# module.net
KiCad netlist of a schematic drawn in EAGLE
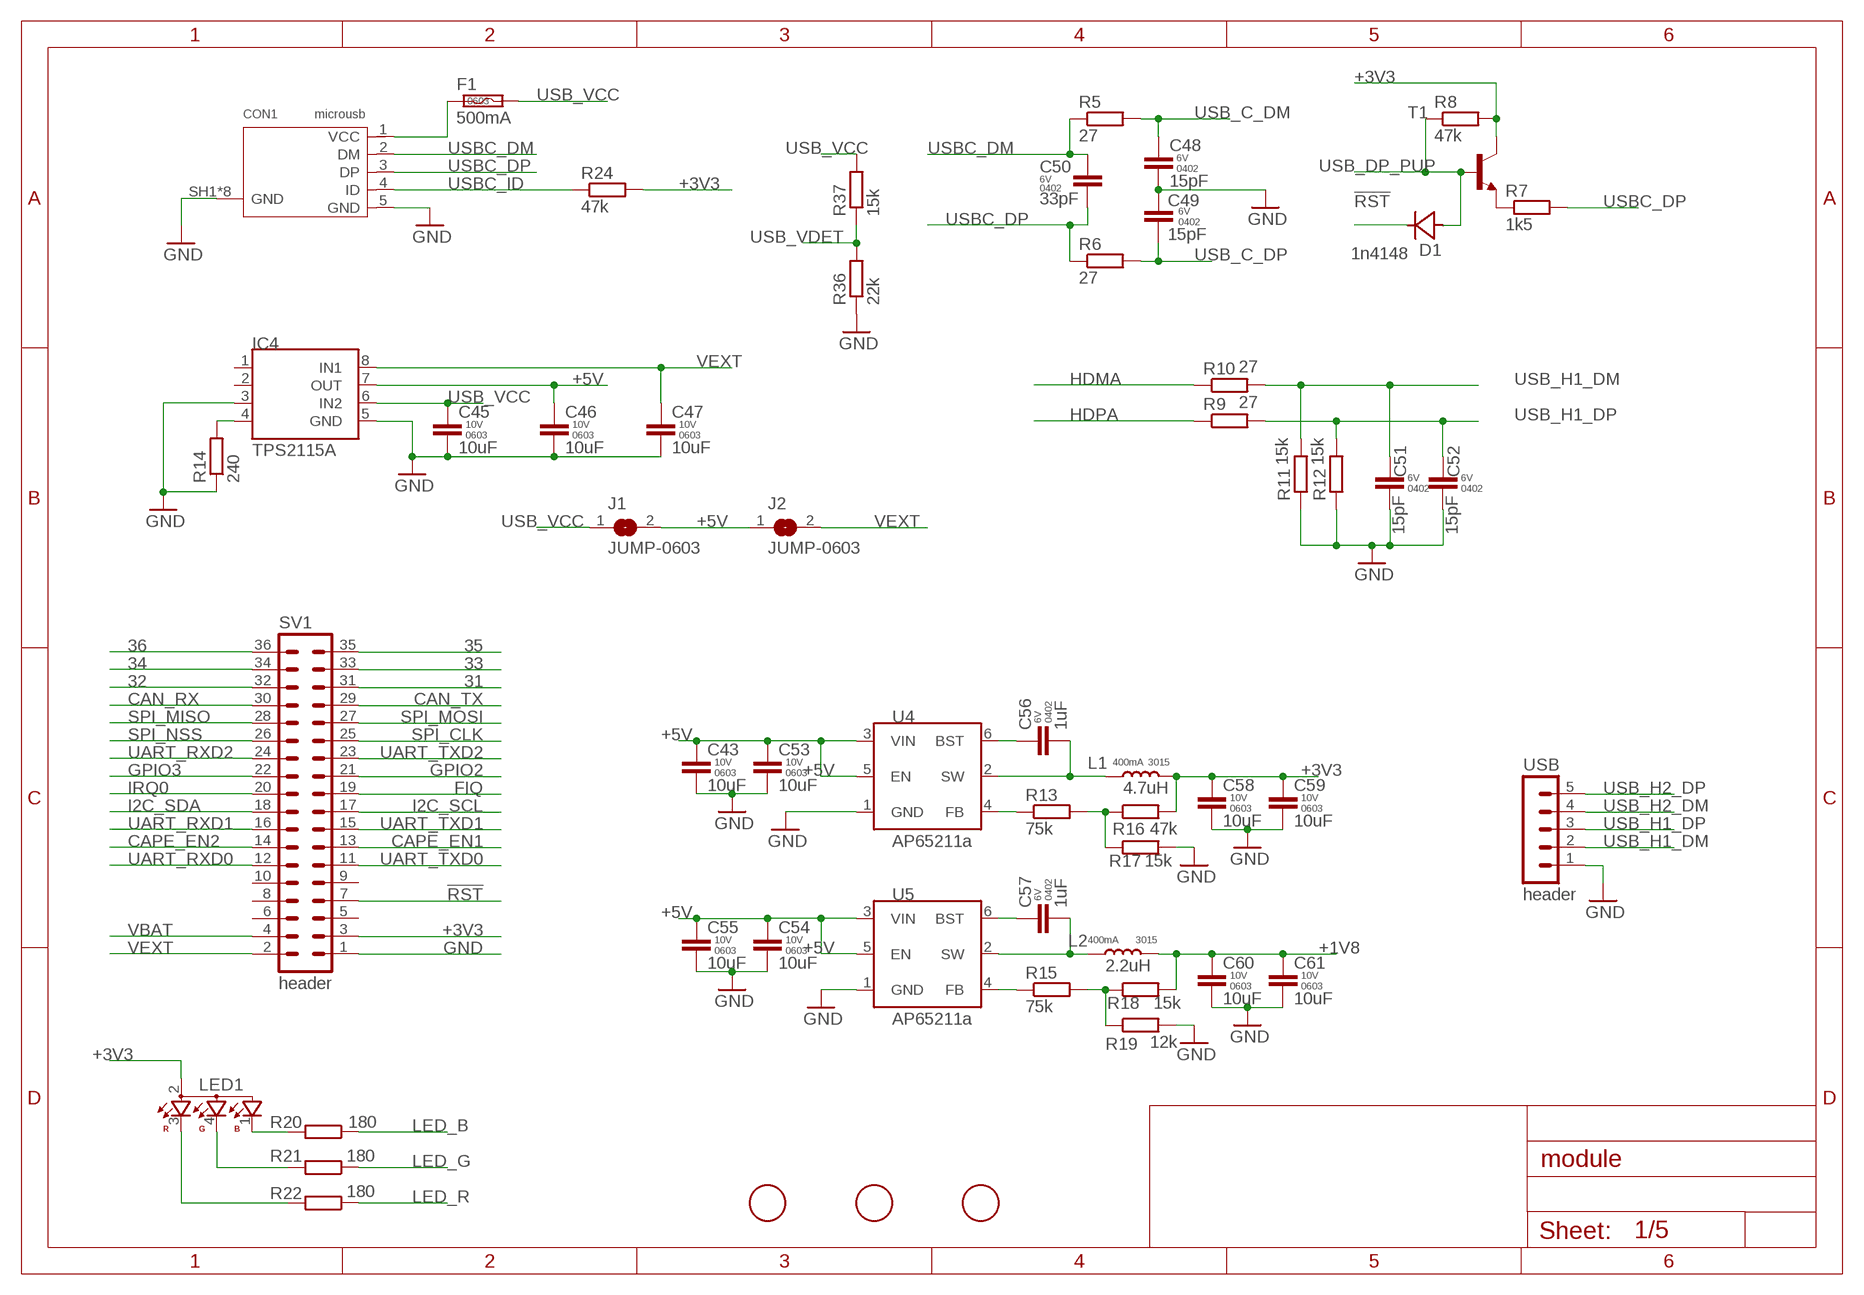
[diagram p0: schematic, sheet 1]
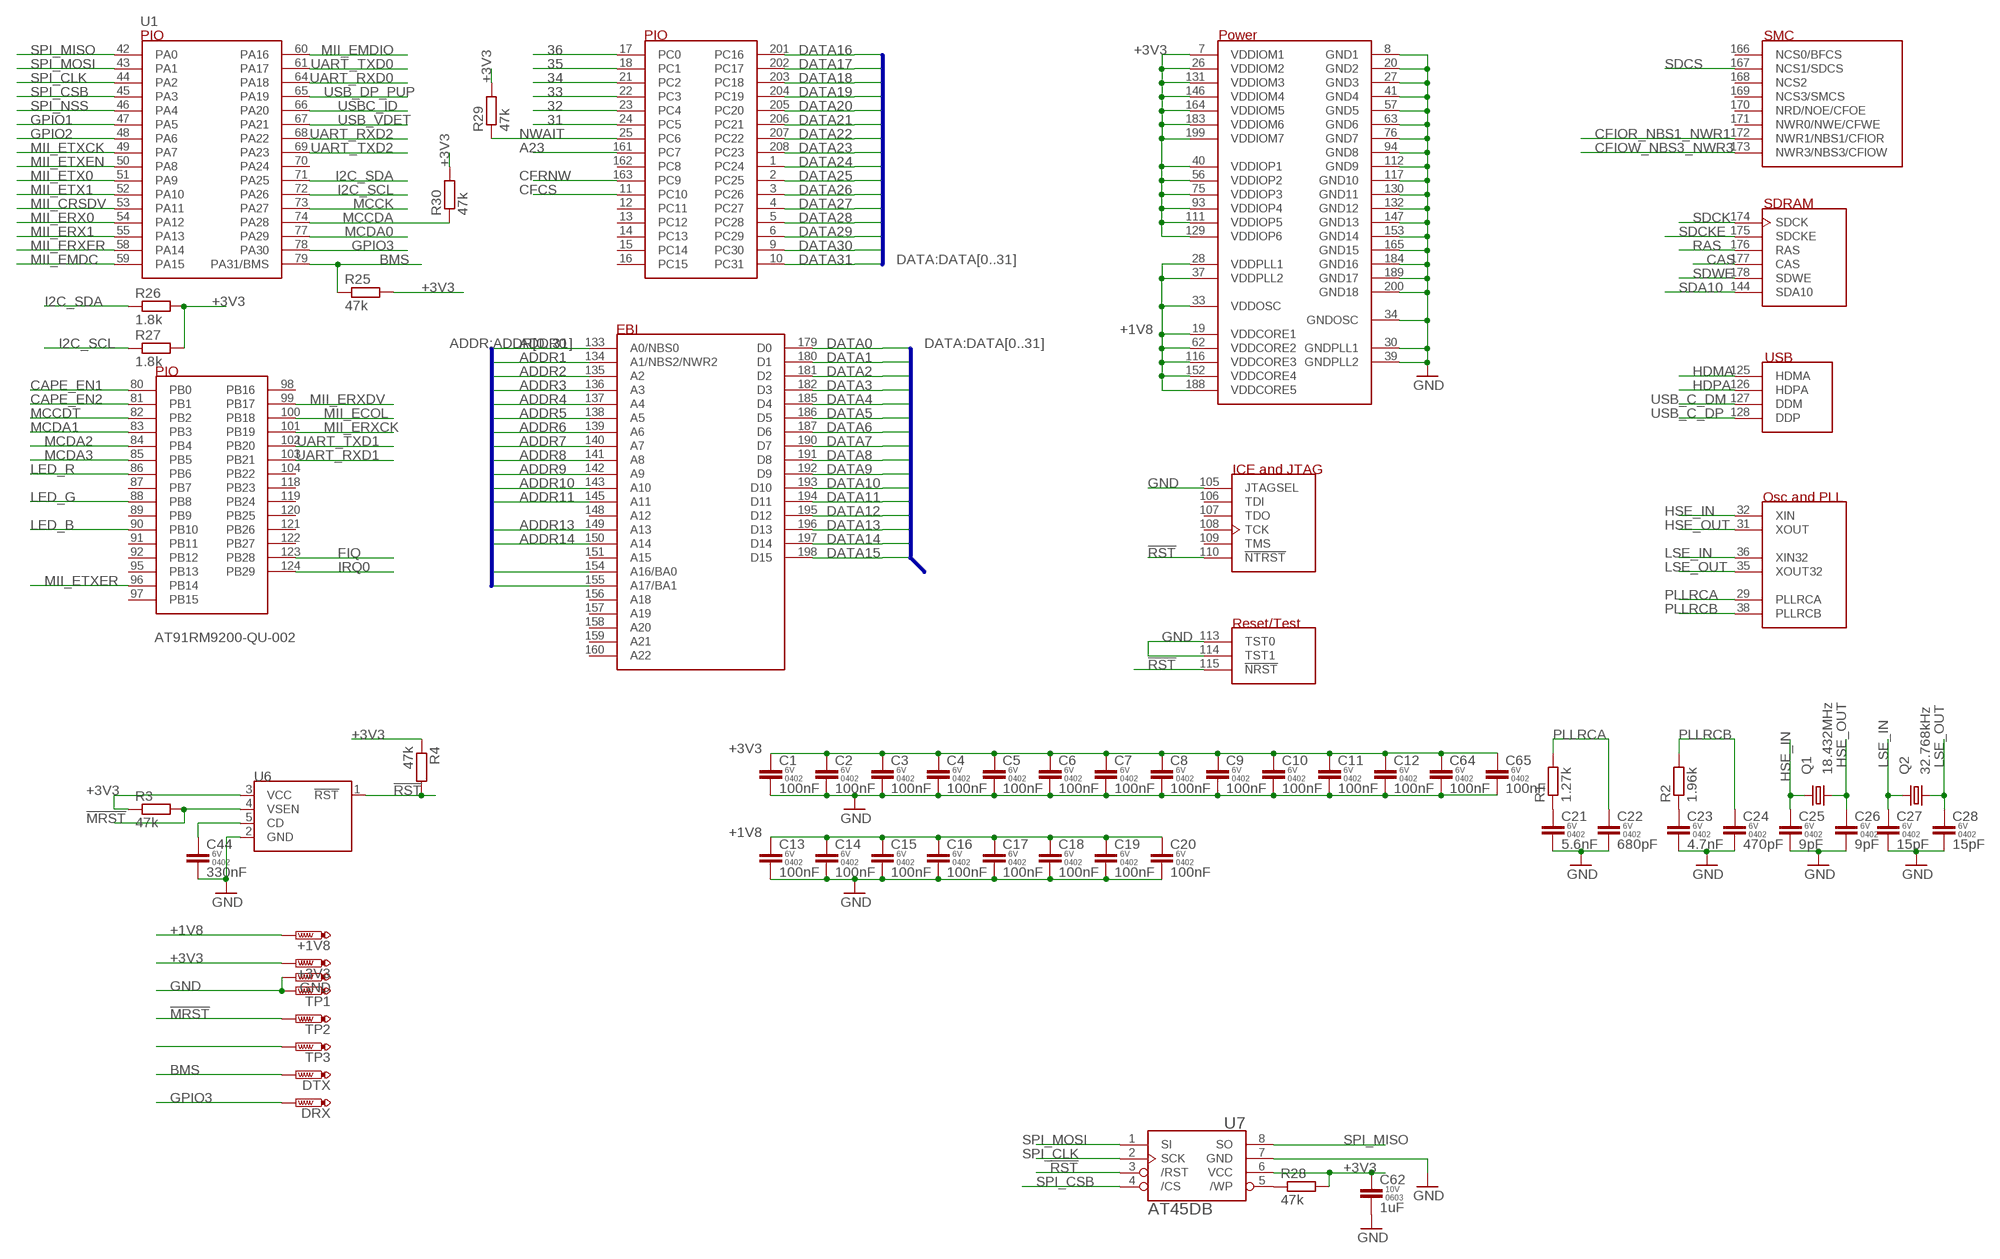
[diagram p1: schematic, sheet 2]
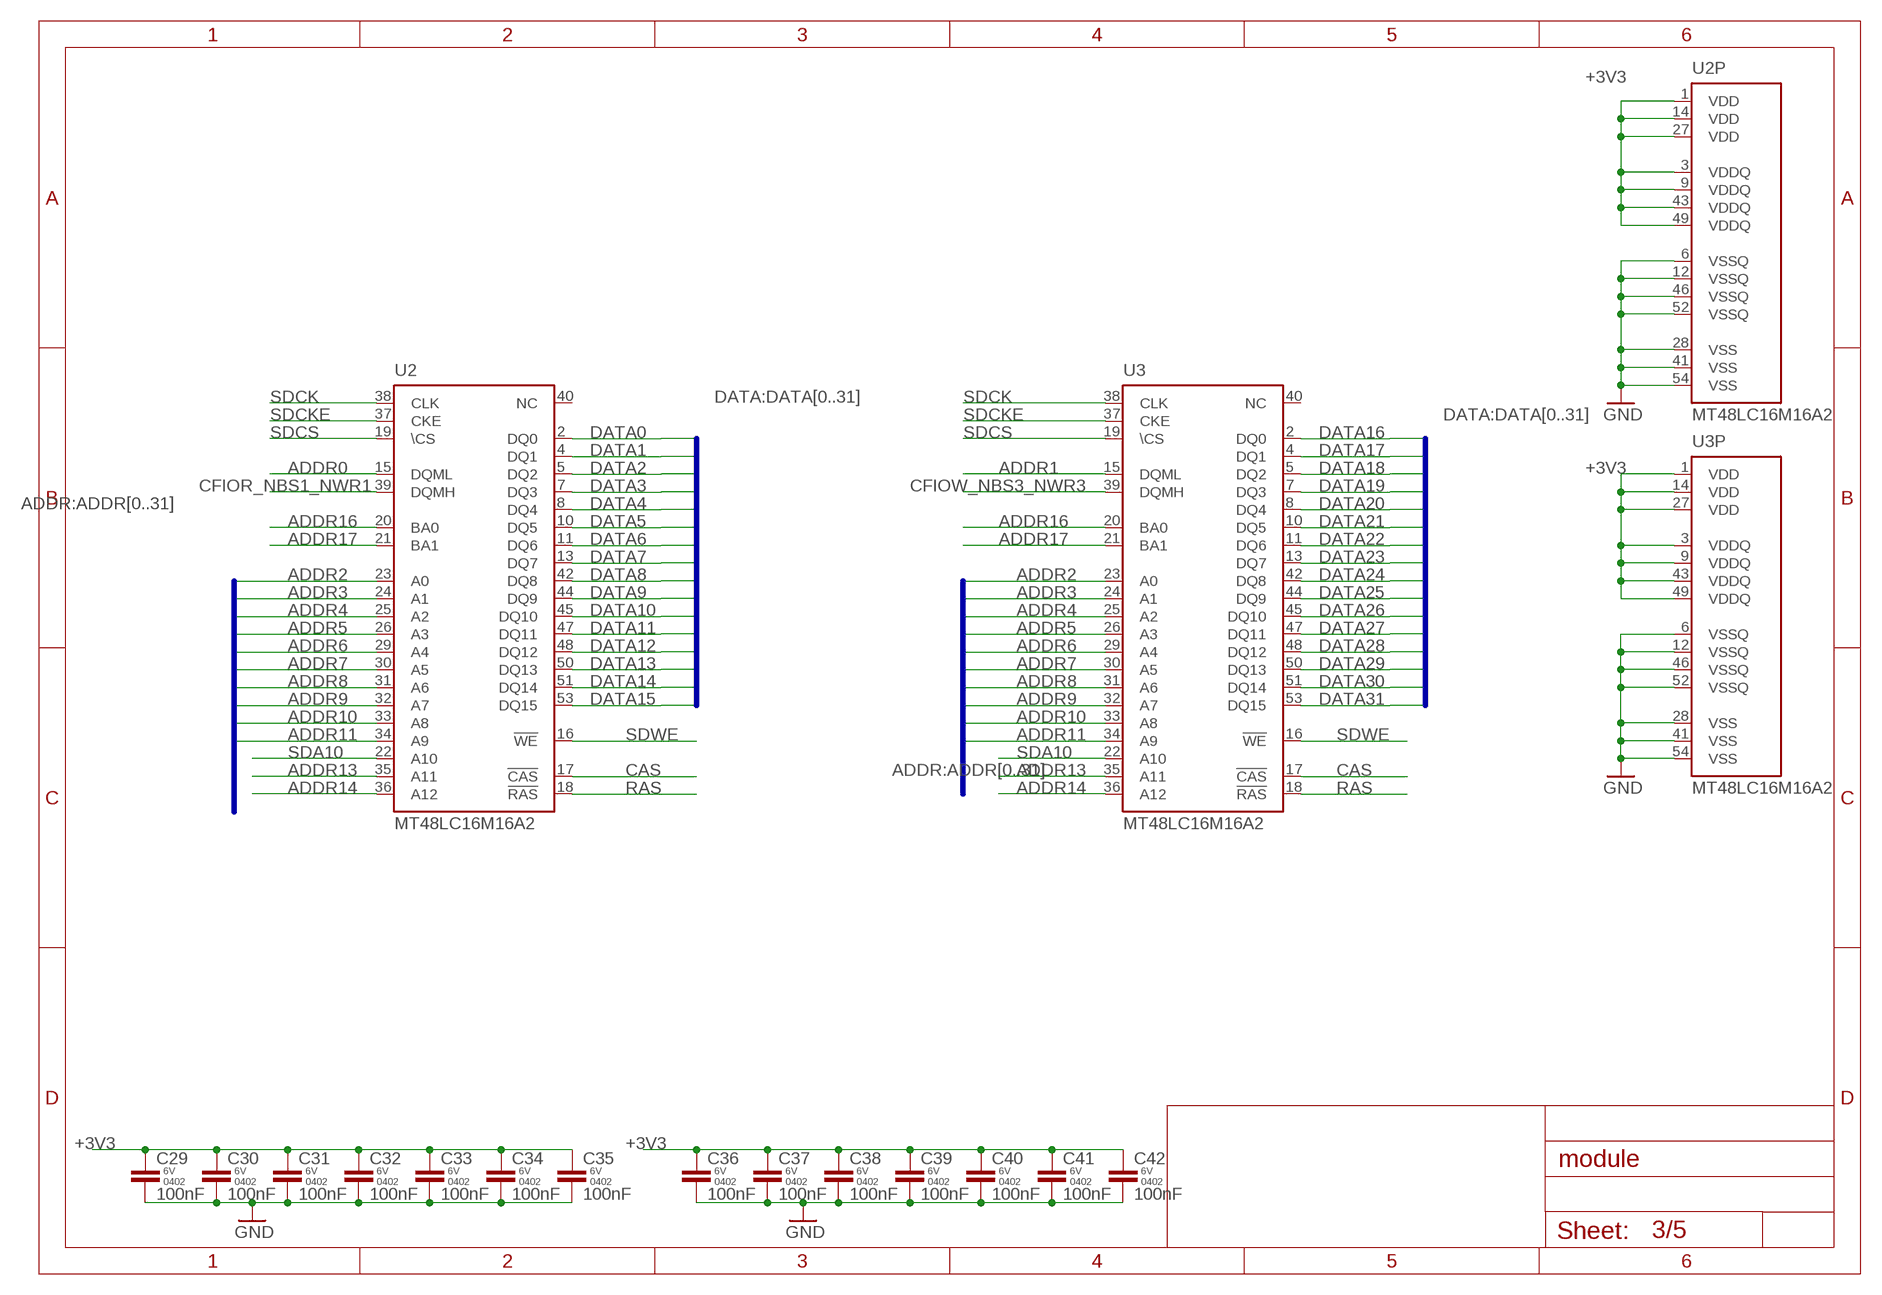
[diagram p2: schematic, sheet 3]
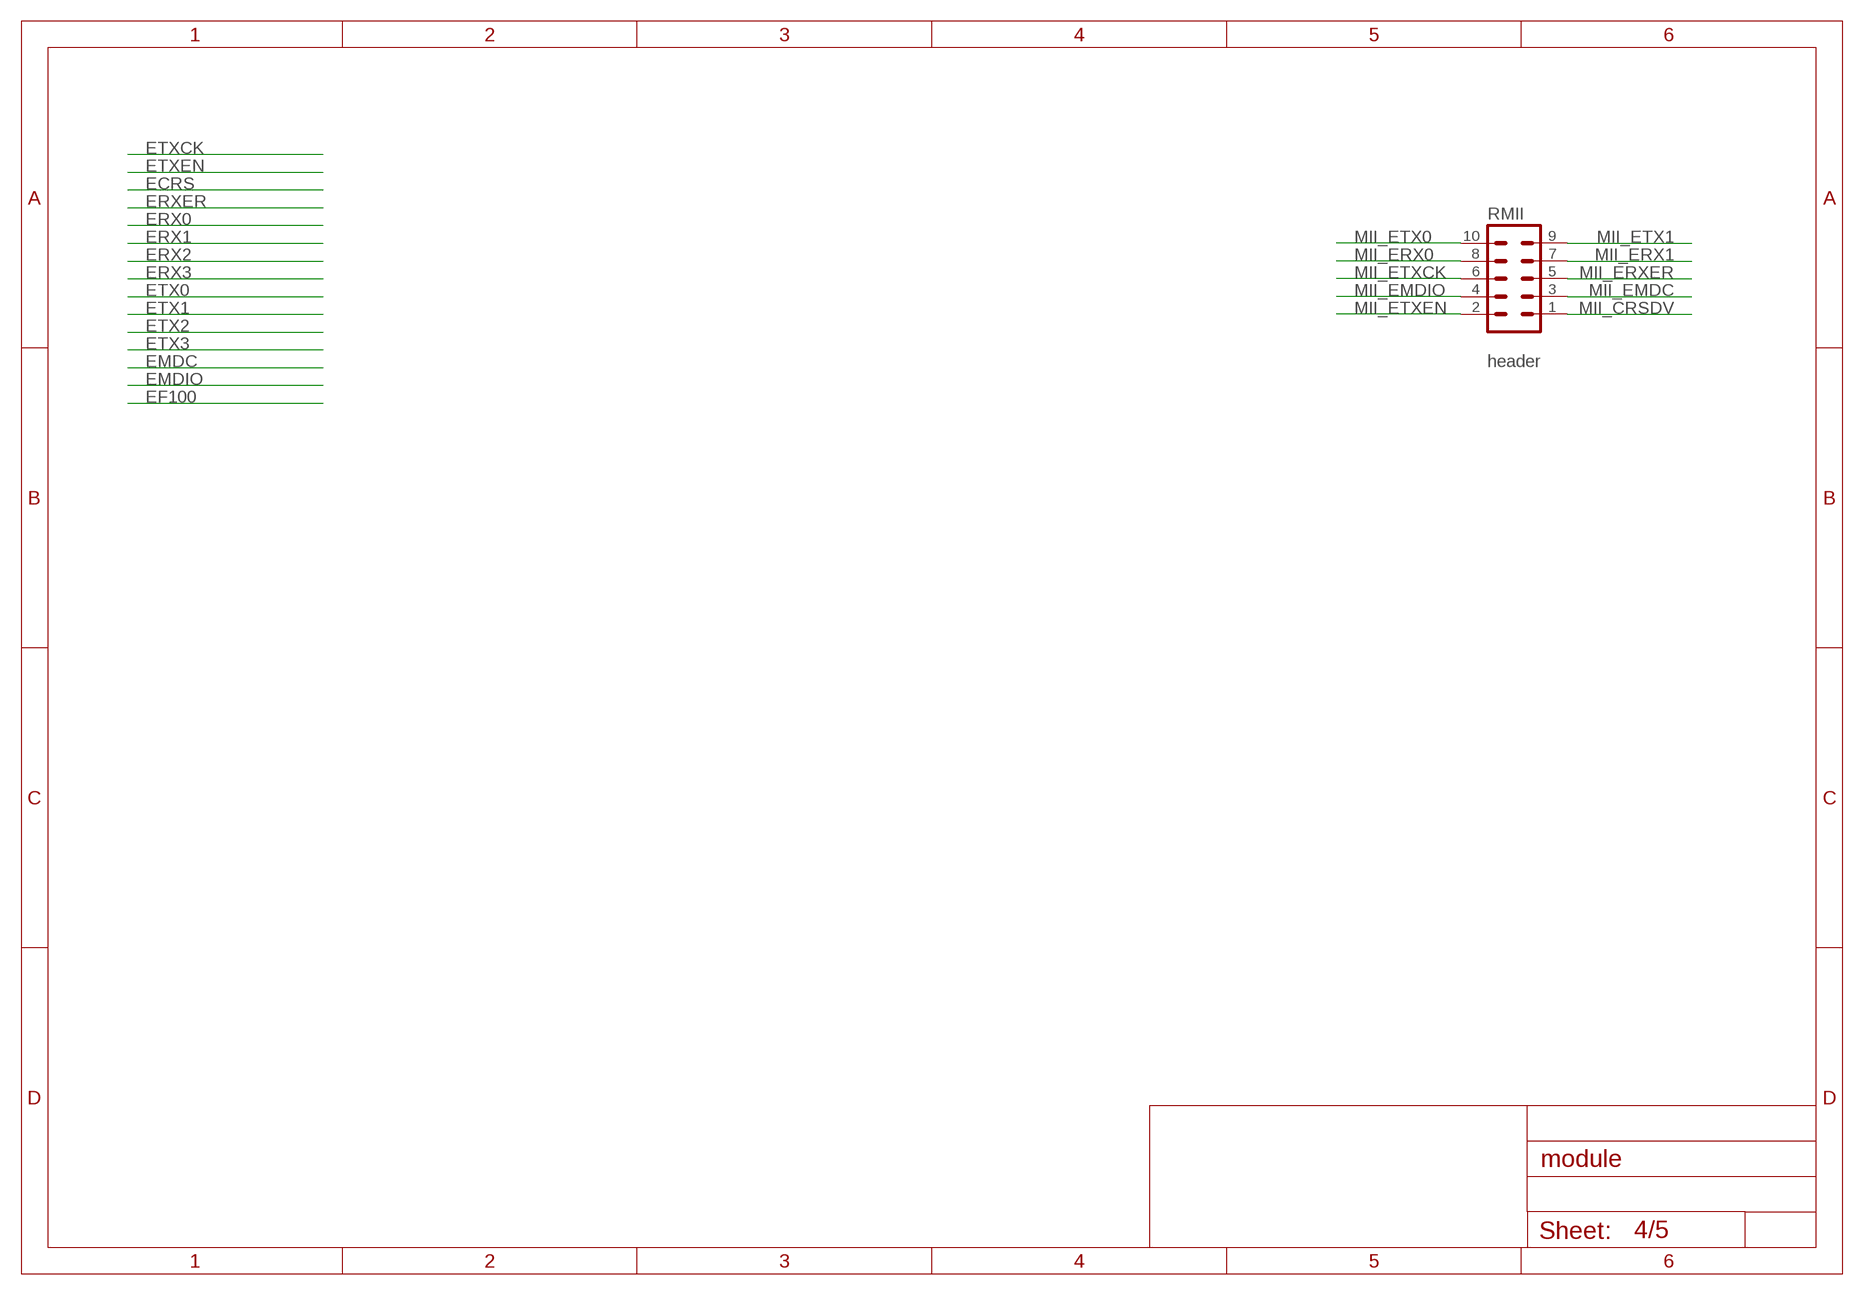
[diagram p3: schematic, sheet 4]
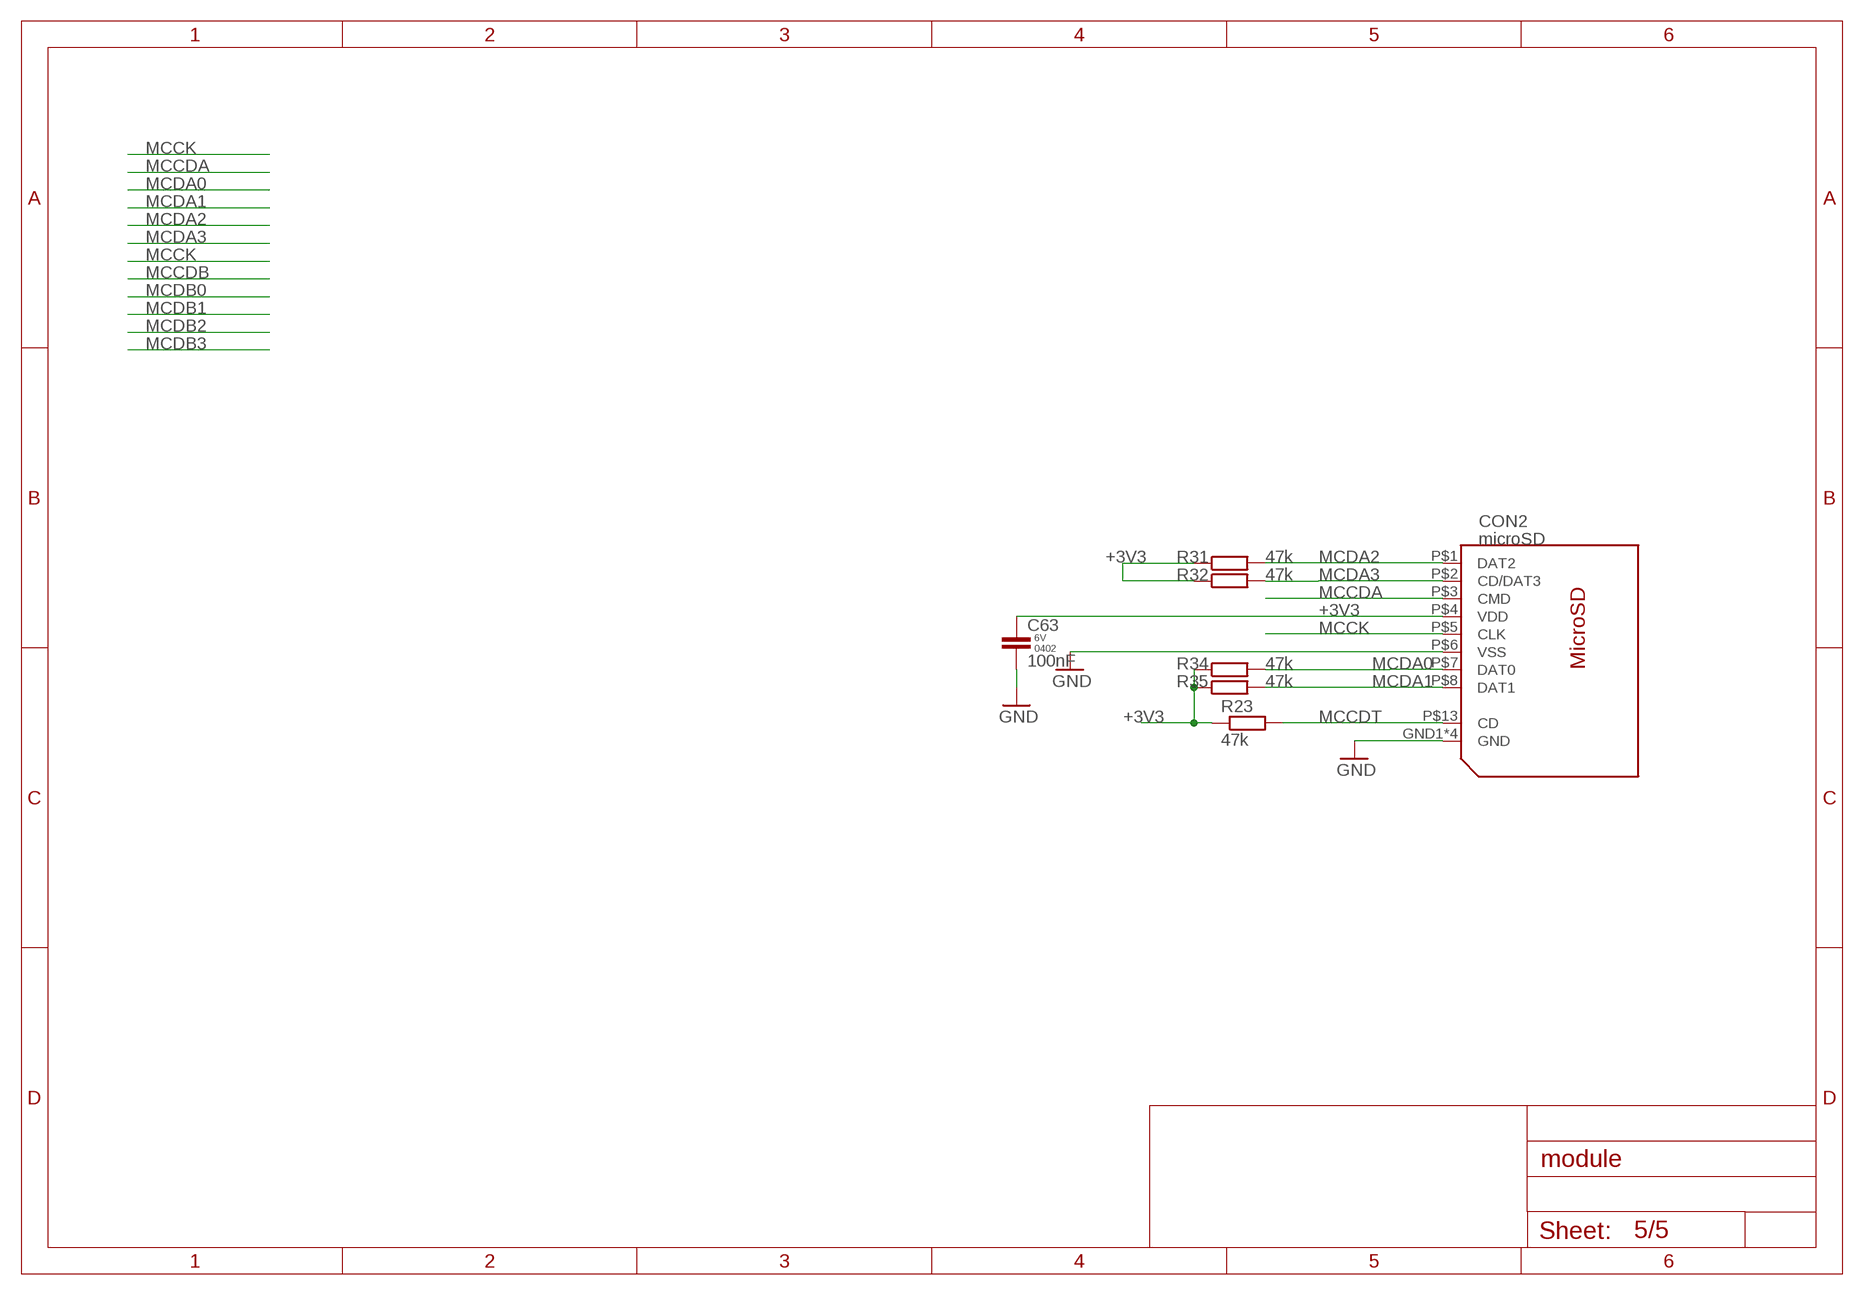
[diagram p4: schematic, sheet 5]

(export (version "E")
  (design (tool "Eeschema 10.0.6"))
  (components
    (comp (ref "+1V8")
      (value "PTR1B1,27")
      (footprint "eagle-import:B1,27")
      (libsource (lib "eagle-import") (part "PTR1B1,27"))
    )
    (comp (ref "+3V3")
      (value "PTR1B1,27")
      (footprint "eagle-import:B1,27")
      (libsource (lib "eagle-import") (part "PTR1B1,27"))
    )
    (comp (ref "C1")
      (value "100nF")
      (footprint "eagle-import:C0402K")
      (fields (field (name "RATING") "6V") (field (name "PACKAGE") "0402"))
      (libsource (lib "eagle-import") (part "CAP-0402"))
    )
    (comp (ref "C2")
      (value "100nF")
      (footprint "eagle-import:C0402K")
      (fields (field (name "RATING") "6V") (field (name "PACKAGE") "0402"))
      (libsource (lib "eagle-import") (part "CAP-0402"))
    )
    (comp (ref "C3")
      (value "100nF")
      (footprint "eagle-import:C0402K")
      (fields (field (name "RATING") "6V") (field (name "PACKAGE") "0402"))
      (libsource (lib "eagle-import") (part "CAP-0402"))
    )
    (comp (ref "C4")
      (value "100nF")
      (footprint "eagle-import:C0402K")
      (fields (field (name "RATING") "6V") (field (name "PACKAGE") "0402"))
      (libsource (lib "eagle-import") (part "CAP-0402"))
    )
    (comp (ref "C5")
      (value "100nF")
      (footprint "eagle-import:C0402K")
      (fields (field (name "RATING") "6V") (field (name "PACKAGE") "0402"))
      (libsource (lib "eagle-import") (part "CAP-0402"))
    )
    (comp (ref "C6")
      (value "100nF")
      (footprint "eagle-import:C0402K")
      (fields (field (name "RATING") "6V") (field (name "PACKAGE") "0402"))
      (libsource (lib "eagle-import") (part "CAP-0402"))
    )
    (comp (ref "C7")
      (value "100nF")
      (footprint "eagle-import:C0402K")
      (fields (field (name "RATING") "6V") (field (name "PACKAGE") "0402"))
      (libsource (lib "eagle-import") (part "CAP-0402"))
    )
    (comp (ref "C8")
      (value "100nF")
      (footprint "eagle-import:C0402K")
      (fields (field (name "RATING") "6V") (field (name "PACKAGE") "0402"))
      (libsource (lib "eagle-import") (part "CAP-0402"))
    )
    (comp (ref "C9")
      (value "100nF")
      (footprint "eagle-import:C0402K")
      (fields (field (name "RATING") "6V") (field (name "PACKAGE") "0402"))
      (libsource (lib "eagle-import") (part "CAP-0402"))
    )
    (comp (ref "C10")
      (value "100nF")
      (footprint "eagle-import:C0402K")
      (fields (field (name "RATING") "6V") (field (name "PACKAGE") "0402"))
      (libsource (lib "eagle-import") (part "CAP-0402"))
    )
    (comp (ref "C11")
      (value "100nF")
      (footprint "eagle-import:C0402K")
      (fields (field (name "RATING") "6V") (field (name "PACKAGE") "0402"))
      (libsource (lib "eagle-import") (part "CAP-0402"))
    )
    (comp (ref "C12")
      (value "100nF")
      (footprint "eagle-import:C0402K")
      (fields (field (name "RATING") "6V") (field (name "PACKAGE") "0402"))
      (libsource (lib "eagle-import") (part "CAP-0402"))
    )
    (comp (ref "C13")
      (value "100nF")
      (footprint "eagle-import:C0402K")
      (fields (field (name "RATING") "6V") (field (name "PACKAGE") "0402"))
      (libsource (lib "eagle-import") (part "CAP-0402"))
    )
    (comp (ref "C14")
      (value "100nF")
      (footprint "eagle-import:C0402K")
      (fields (field (name "RATING") "6V") (field (name "PACKAGE") "0402"))
      (libsource (lib "eagle-import") (part "CAP-0402"))
    )
    (comp (ref "C15")
      (value "100nF")
      (footprint "eagle-import:C0402K")
      (fields (field (name "RATING") "6V") (field (name "PACKAGE") "0402"))
      (libsource (lib "eagle-import") (part "CAP-0402"))
    )
    (comp (ref "C16")
      (value "100nF")
      (footprint "eagle-import:C0402K")
      (fields (field (name "RATING") "6V") (field (name "PACKAGE") "0402"))
      (libsource (lib "eagle-import") (part "CAP-0402"))
    )
    (comp (ref "C17")
      (value "100nF")
      (footprint "eagle-import:C0402K")
      (fields (field (name "RATING") "6V") (field (name "PACKAGE") "0402"))
      (libsource (lib "eagle-import") (part "CAP-0402"))
    )
    (comp (ref "C18")
      (value "100nF")
      (footprint "eagle-import:C0402K")
      (fields (field (name "RATING") "6V") (field (name "PACKAGE") "0402"))
      (libsource (lib "eagle-import") (part "CAP-0402"))
    )
    (comp (ref "C19")
      (value "100nF")
      (footprint "eagle-import:C0402K")
      (fields (field (name "RATING") "6V") (field (name "PACKAGE") "0402"))
      (libsource (lib "eagle-import") (part "CAP-0402"))
    )
    (comp (ref "C20")
      (value "100nF")
      (footprint "eagle-import:C0402K")
      (fields (field (name "RATING") "6V") (field (name "PACKAGE") "0402"))
      (libsource (lib "eagle-import") (part "CAP-0402"))
    )
    (comp (ref "C21")
      (value "5.6nF")
      (footprint "eagle-import:C0402K")
      (fields (field (name "RATING") "6V") (field (name "PACKAGE") "0402"))
      (libsource (lib "eagle-import") (part "CAP-0402"))
    )
    (comp (ref "C22")
      (value "680pF")
      (footprint "eagle-import:C0402K")
      (fields (field (name "RATING") "6V") (field (name "PACKAGE") "0402"))
      (libsource (lib "eagle-import") (part "CAP-0402"))
    )
    (comp (ref "C23")
      (value "4.7nF")
      (footprint "eagle-import:C0402K")
      (fields (field (name "RATING") "6V") (field (name "PACKAGE") "0402"))
      (libsource (lib "eagle-import") (part "CAP-0402"))
    )
    (comp (ref "C24")
      (value "470pF")
      (footprint "eagle-import:C0402K")
      (fields (field (name "RATING") "6V") (field (name "PACKAGE") "0402"))
      (libsource (lib "eagle-import") (part "CAP-0402"))
    )
    (comp (ref "C25")
      (value "9pF")
      (footprint "eagle-import:C0402K")
      (fields (field (name "RATING") "6V") (field (name "PACKAGE") "0402"))
      (libsource (lib "eagle-import") (part "CAP-0402"))
    )
    (comp (ref "C26")
      (value "9pF")
      (footprint "eagle-import:C0402K")
      (fields (field (name "RATING") "6V") (field (name "PACKAGE") "0402"))
      (libsource (lib "eagle-import") (part "CAP-0402"))
    )
    (comp (ref "C27")
      (value "15pF")
      (footprint "eagle-import:C0402K")
      (fields (field (name "RATING") "6V") (field (name "PACKAGE") "0402"))
      (libsource (lib "eagle-import") (part "CAP-0402"))
    )
    (comp (ref "C28")
      (value "15pF")
      (footprint "eagle-import:C0402K")
      (fields (field (name "RATING") "6V") (field (name "PACKAGE") "0402"))
      (libsource (lib "eagle-import") (part "CAP-0402"))
    )
    (comp (ref "C44")
      (value "330nF")
      (footprint "eagle-import:C0402K")
      (fields (field (name "RATING") "6V") (field (name "PACKAGE") "0402"))
      (libsource (lib "eagle-import") (part "CAP-0402"))
    )
    (comp (ref "C62")
      (value "1uF")
      (footprint "eagle-import:C0603")
      (fields (field (name "RATING") "10V") (field (name "PACKAGE") "0603"))
      (libsource (lib "eagle-import") (part "CAP-0603"))
    )
    (comp (ref "C64")
      (value "100nF")
      (footprint "eagle-import:C0402K")
      (fields (field (name "RATING") "6V") (field (name "PACKAGE") "0402"))
      (libsource (lib "eagle-import") (part "CAP-0402"))
    )
    (comp (ref "C65")
      (value "100nF")
      (footprint "eagle-import:C0402K")
      (fields (field (name "RATING") "6V") (field (name "PACKAGE") "0402"))
      (libsource (lib "eagle-import") (part "CAP-0402"))
    )
    (comp (ref "DRX")
      (value "PTR1B1,27")
      (footprint "eagle-import:B1,27")
      (libsource (lib "eagle-import") (part "PTR1B1,27"))
    )
    (comp (ref "DTX")
      (value "PTR1B1,27")
      (footprint "eagle-import:B1,27")
      (libsource (lib "eagle-import") (part "PTR1B1,27"))
    )
    (comp (ref "GND")
      (value "PTR1B1,27")
      (footprint "eagle-import:B1,27")
      (libsource (lib "eagle-import") (part "PTR1B1,27"))
    )
    (comp (ref "Q1")
      (value "18.432MHz")
      (footprint "eagle-import:3215")
      (libsource (lib "eagle-import") (part "3215-7"))
    )
    (comp (ref "Q2")
      (value "32.768kHz")
      (footprint "eagle-import:3215")
      (libsource (lib "eagle-import") (part "CFPX–217-NHT"))
    )
    (comp (ref "R1")
      (value "1.27k")
      (footprint "eagle-import:R0402")
      (libsource (lib "eagle-import") (part "R-EU_R0402"))
    )
    (comp (ref "R2")
      (value "1.96k")
      (footprint "eagle-import:R0402")
      (libsource (lib "eagle-import") (part "R-EU_R0402"))
    )
    (comp (ref "R3")
      (value "47k")
      (footprint "eagle-import:R0402")
      (libsource (lib "eagle-import") (part "R-EU_R0402"))
    )
    (comp (ref "R4")
      (value "47k")
      (footprint "eagle-import:R0402")
      (libsource (lib "eagle-import") (part "R-EU_R0402"))
    )
    (comp (ref "R25")
      (value "47k")
      (footprint "eagle-import:R0402")
      (libsource (lib "eagle-import") (part "R-EU_R0402"))
    )
    (comp (ref "R26")
      (value "1.8k")
      (footprint "eagle-import:R0402")
      (libsource (lib "eagle-import") (part "R-EU_R0402"))
    )
    (comp (ref "R27")
      (value "1.8k")
      (footprint "eagle-import:R0402")
      (libsource (lib "eagle-import") (part "R-EU_R0402"))
    )
    (comp (ref "R28")
      (value "47k")
      (footprint "eagle-import:R0402")
      (libsource (lib "eagle-import") (part "R-EU_R0402"))
    )
    (comp (ref "R29")
      (value "47k")
      (footprint "eagle-import:R0402")
      (libsource (lib "eagle-import") (part "R-EU_R0402"))
    )
    (comp (ref "R30")
      (value "47k")
      (footprint "eagle-import:R0402")
      (libsource (lib "eagle-import") (part "R-EU_R0402"))
    )
    (comp (ref "TP1")
      (value "PTR1B1,27")
      (footprint "eagle-import:B1,27")
      (libsource (lib "eagle-import") (part "PTR1B1,27"))
    )
    (comp (ref "TP2")
      (value "PTR1B1,27")
      (footprint "eagle-import:B1,27")
      (libsource (lib "eagle-import") (part "PTR1B1,27"))
    )
    (comp (ref "TP3")
      (value "PTR1B1,27")
      (footprint "eagle-import:B1,27")
      (libsource (lib "eagle-import") (part "PTR1B1,27"))
    )
    (comp (ref "U1")
      (value "AT91RM9200-QU-002")
      (footprint "eagle-import:QFP50P3120X3120X410-208N")
      (fields (field (name "MF") "Microchip"))
      (libsource (lib "eagle-import") (part "AT91RM9200-QU-002"))
    )
    (comp (ref "U6")
      (value "STM1831")
      (footprint "eagle-import:SOT95P280X100-5")
      (libsource (lib "eagle-import") (part "STM1831"))
    )
    (comp (ref "U7")
      (value "AT45DB-S")
      (footprint "eagle-import:SO08-208")
      (libsource (lib "eagle-import") (part "AT45DB-S"))
    )
    (comp (ref "C43")
      (value "10uF")
      (footprint "eagle-import:C0603")
      (fields (field (name "RATING") "10V") (field (name "PACKAGE") "0603"))
      (libsource (lib "eagle-import") (part "CAP-0603"))
    )
    (comp (ref "C45")
      (value "10uF")
      (footprint "eagle-import:C0603")
      (fields (field (name "RATING") "10V") (field (name "PACKAGE") "0603"))
      (libsource (lib "eagle-import") (part "CAP-0603"))
    )
    (comp (ref "C46")
      (value "10uF")
      (footprint "eagle-import:C0603")
      (fields (field (name "RATING") "10V") (field (name "PACKAGE") "0603"))
      (libsource (lib "eagle-import") (part "CAP-0603"))
    )
    (comp (ref "C47")
      (value "10uF")
      (footprint "eagle-import:C0603")
      (fields (field (name "RATING") "10V") (field (name "PACKAGE") "0603"))
      (libsource (lib "eagle-import") (part "CAP-0603"))
    )
    (comp (ref "C48")
      (value "15pF")
      (footprint "eagle-import:C0402K")
      (fields (field (name "RATING") "6V") (field (name "PACKAGE") "0402"))
      (libsource (lib "eagle-import") (part "CAP-0402"))
    )
    (comp (ref "C49")
      (value "15pF")
      (footprint "eagle-import:C0402K")
      (fields (field (name "RATING") "6V") (field (name "PACKAGE") "0402"))
      (libsource (lib "eagle-import") (part "CAP-0402"))
    )
    (comp (ref "C50")
      (value "33pF")
      (footprint "eagle-import:C0402K")
      (fields (field (name "RATING") "6V") (field (name "PACKAGE") "0402"))
      (libsource (lib "eagle-import") (part "CAP-0402"))
    )
    (comp (ref "C51")
      (value "15pF")
      (footprint "eagle-import:C0402K")
      (fields (field (name "RATING") "6V") (field (name "PACKAGE") "0402"))
      (libsource (lib "eagle-import") (part "CAP-0402"))
    )
    (comp (ref "C52")
      (value "15pF")
      (footprint "eagle-import:C0402K")
      (fields (field (name "RATING") "6V") (field (name "PACKAGE") "0402"))
      (libsource (lib "eagle-import") (part "CAP-0402"))
    )
    (comp (ref "C53")
      (value "10uF")
      (footprint "eagle-import:C0603")
      (fields (field (name "RATING") "10V") (field (name "PACKAGE") "0603"))
      (libsource (lib "eagle-import") (part "CAP-0603"))
    )
    (comp (ref "C54")
      (value "10uF")
      (footprint "eagle-import:C0603")
      (fields (field (name "RATING") "10V") (field (name "PACKAGE") "0603"))
      (libsource (lib "eagle-import") (part "CAP-0603"))
    )
    (comp (ref "C55")
      (value "10uF")
      (footprint "eagle-import:C0603")
      (fields (field (name "RATING") "10V") (field (name "PACKAGE") "0603"))
      (libsource (lib "eagle-import") (part "CAP-0603"))
    )
    (comp (ref "C56")
      (value "1uF")
      (footprint "eagle-import:C0402K")
      (fields (field (name "RATING") "6V") (field (name "PACKAGE") "0402"))
      (libsource (lib "eagle-import") (part "CAP-0402"))
    )
    (comp (ref "C57")
      (value "1uF")
      (footprint "eagle-import:C0402K")
      (fields (field (name "RATING") "6V") (field (name "PACKAGE") "0402"))
      (libsource (lib "eagle-import") (part "CAP-0402"))
    )
    (comp (ref "C58")
      (value "10uF")
      (footprint "eagle-import:C0603")
      (fields (field (name "RATING") "10V") (field (name "PACKAGE") "0603"))
      (libsource (lib "eagle-import") (part "CAP-0603"))
    )
    (comp (ref "C59")
      (value "10uF")
      (footprint "eagle-import:C0603")
      (fields (field (name "RATING") "10V") (field (name "PACKAGE") "0603"))
      (libsource (lib "eagle-import") (part "CAP-0603"))
    )
    (comp (ref "C60")
      (value "10uF")
      (footprint "eagle-import:C0603")
      (fields (field (name "RATING") "10V") (field (name "PACKAGE") "0603"))
      (libsource (lib "eagle-import") (part "CAP-0603"))
    )
    (comp (ref "C61")
      (value "10uF")
      (footprint "eagle-import:C0603")
      (fields (field (name "RATING") "10V") (field (name "PACKAGE") "0603"))
      (libsource (lib "eagle-import") (part "CAP-0603"))
    )
    (comp (ref "CON1")
      (value "microusb")
      (footprint "eagle-import:10118194")
      (libsource (lib "eagle-import") (part "10118194-0001LF"))
    )
    (comp (ref "D1")
      (value "1n4148")
      (footprint "eagle-import:SOD323")
      (libsource (lib "eagle-import") (part "1N4148WS"))
    )
    (comp (ref "F1")
      (value "500mA")
      (footprint "eagle-import:F0603")
      (fields (field (name "PACKAGE") "0603"))
      (libsource (lib "eagle-import") (part "FUSE-PTC-0603"))
    )
    (comp (ref "IC4")
      (value "TPS2115A")
      (footprint "eagle-import:TSSOP8")
      (libsource (lib "eagle-import") (part "TPS2115A"))
    )
    (comp (ref "J1")
      (value "JUMP-0603")
      (footprint "eagle-import:C0603")
      (libsource (lib "eagle-import") (part "JUMP-0603"))
    )
    (comp (ref "J2")
      (value "JUMP-0603")
      (footprint "eagle-import:C0603")
      (libsource (lib "eagle-import") (part "JUMP-0603"))
    )
    (comp (ref "L1")
      (value "4.7uH")
      (footprint "eagle-import:L3230M")
      (fields (field (name "PACKAGE") "3015") (field (name "CURRENT") "400mA"))
      (libsource (lib "eagle-import") (part "DJNR3015"))
    )
    (comp (ref "L2")
      (value "2.2uH")
      (footprint "eagle-import:L3230M")
      (fields (field (name "PACKAGE") "3015") (field (name "CURRENT") "400mA"))
      (libsource (lib "eagle-import") (part "DJNR3015"))
    )
    (comp (ref "LED1")
      (value "OSTB1204C1E")
      (footprint "eagle-import:321015RGB")
      (libsource (lib "eagle-import") (part "OSTB1204C1E"))
    )
    (comp (ref "R5")
      (value "27")
      (footprint "eagle-import:R0402")
      (libsource (lib "eagle-import") (part "R-EU_R0402"))
    )
    (comp (ref "R6")
      (value "27")
      (footprint "eagle-import:R0402")
      (libsource (lib "eagle-import") (part "R-EU_R0402"))
    )
    (comp (ref "R7")
      (value "1k5")
      (footprint "eagle-import:R0402")
      (libsource (lib "eagle-import") (part "R-EU_R0402"))
    )
    (comp (ref "R8")
      (value "47k")
      (footprint "eagle-import:R0402")
      (libsource (lib "eagle-import") (part "R-EU_R0402"))
    )
    (comp (ref "R9")
      (value "27")
      (footprint "eagle-import:R0402")
      (libsource (lib "eagle-import") (part "R-EU_R0402"))
    )
    (comp (ref "R10")
      (value "27")
      (footprint "eagle-import:R0402")
      (libsource (lib "eagle-import") (part "R-EU_R0402"))
    )
    (comp (ref "R11")
      (value "15k")
      (footprint "eagle-import:R0402")
      (libsource (lib "eagle-import") (part "R-EU_R0402"))
    )
    (comp (ref "R12")
      (value "15k")
      (footprint "eagle-import:R0402")
      (libsource (lib "eagle-import") (part "R-EU_R0402"))
    )
    (comp (ref "R13")
      (value "75k")
      (footprint "eagle-import:R0402")
      (libsource (lib "eagle-import") (part "R-EU_R0402"))
    )
    (comp (ref "R14")
      (value "240")
      (footprint "eagle-import:R0402")
      (libsource (lib "eagle-import") (part "R-EU_R0402"))
    )
    (comp (ref "R15")
      (value "75k")
      (footprint "eagle-import:R0402")
      (libsource (lib "eagle-import") (part "R-EU_R0402"))
    )
    (comp (ref "R16")
      (value "47k")
      (footprint "eagle-import:R0402")
      (libsource (lib "eagle-import") (part "R-EU_R0402"))
    )
    (comp (ref "R17")
      (value "15k")
      (footprint "eagle-import:R0402")
      (libsource (lib "eagle-import") (part "R-EU_R0402"))
    )
    (comp (ref "R18")
      (value "15k")
      (footprint "eagle-import:R0402")
      (libsource (lib "eagle-import") (part "R-EU_R0402"))
    )
    (comp (ref "R19")
      (value "12k")
      (footprint "eagle-import:R0402")
      (libsource (lib "eagle-import") (part "R-EU_R0402"))
    )
    (comp (ref "R20")
      (value "180")
      (footprint "eagle-import:R0402")
      (libsource (lib "eagle-import") (part "R-EU_R0402"))
    )
    (comp (ref "R21")
      (value "180")
      (footprint "eagle-import:R0402")
      (libsource (lib "eagle-import") (part "R-EU_R0402"))
    )
    (comp (ref "R22")
      (value "180")
      (footprint "eagle-import:R0402")
      (libsource (lib "eagle-import") (part "R-EU_R0402"))
    )
    (comp (ref "R24")
      (value "47k")
      (footprint "eagle-import:R0402")
      (libsource (lib "eagle-import") (part "R-EU_R0402"))
    )
    (comp (ref "R36")
      (value "22k")
      (footprint "eagle-import:R0402")
      (libsource (lib "eagle-import") (part "R-EU_R0402"))
    )
    (comp (ref "R37")
      (value "15k")
      (footprint "eagle-import:R0402")
      (libsource (lib "eagle-import") (part "R-EU_R0402"))
    )
    (comp (ref "SV1")
      (value "header")
      (footprint "eagle-import:MA18-2")
      (libsource (lib "eagle-import") (part "MA18-2"))
    )
    (comp (ref "T1")
      (value "MMBT2222ALT1-NPN-SOT23-BEC")
      (footprint "eagle-import:SOT23-BEC")
      (libsource (lib "eagle-import") (part "-NPN-SOT23-BECMMBT2222ALT1"))
    )
    (comp (ref "U$1")
      (value "FIDUCIAL")
      (footprint "eagle-import:FIDUCIAL_1MM")
      (libsource (lib "eagle-import") (part "FIDUCIAL"))
    )
    (comp (ref "U$2")
      (value "FIDUCIAL")
      (footprint "eagle-import:FIDUCIAL_1MM")
      (libsource (lib "eagle-import") (part "FIDUCIAL"))
    )
    (comp (ref "U$3")
      (value "FIDUCIAL")
      (footprint "eagle-import:FIDUCIAL_1MM")
      (libsource (lib "eagle-import") (part "FIDUCIAL"))
    )
    (comp (ref "U4")
      (value "AP65211A")
      (footprint "eagle-import:SOT95P280X110-6")
      (libsource (lib "eagle-import") (part "AP65211"))
    )
    (comp (ref "U5")
      (value "AP65211A")
      (footprint "eagle-import:SOT95P280X110-6")
      (libsource (lib "eagle-import") (part "AP65211"))
    )
    (comp (ref "USB")
      (value "header")
      (footprint "eagle-import:MA05-1")
      (libsource (lib "eagle-import") (part "MA05-1"))
    )
    (comp (ref "RMII")
      (value "header")
      (footprint "eagle-import:MA05-2")
      (libsource (lib "eagle-import") (part "MA05-2"))
    )
    (comp (ref "C29")
      (value "100nF")
      (footprint "eagle-import:C0402K")
      (fields (field (name "RATING") "6V") (field (name "PACKAGE") "0402"))
      (libsource (lib "eagle-import") (part "CAP-0402"))
    )
    (comp (ref "C30")
      (value "100nF")
      (footprint "eagle-import:C0402K")
      (fields (field (name "RATING") "6V") (field (name "PACKAGE") "0402"))
      (libsource (lib "eagle-import") (part "CAP-0402"))
    )
    (comp (ref "C31")
      (value "100nF")
      (footprint "eagle-import:C0402K")
      (fields (field (name "RATING") "6V") (field (name "PACKAGE") "0402"))
      (libsource (lib "eagle-import") (part "CAP-0402"))
    )
    (comp (ref "C32")
      (value "100nF")
      (footprint "eagle-import:C0402K")
      (fields (field (name "RATING") "6V") (field (name "PACKAGE") "0402"))
      (libsource (lib "eagle-import") (part "CAP-0402"))
    )
    (comp (ref "C33")
      (value "100nF")
      (footprint "eagle-import:C0402K")
      (fields (field (name "RATING") "6V") (field (name "PACKAGE") "0402"))
      (libsource (lib "eagle-import") (part "CAP-0402"))
    )
    (comp (ref "C34")
      (value "100nF")
      (footprint "eagle-import:C0402K")
      (fields (field (name "RATING") "6V") (field (name "PACKAGE") "0402"))
      (libsource (lib "eagle-import") (part "CAP-0402"))
    )
    (comp (ref "C35")
      (value "100nF")
      (footprint "eagle-import:C0402K")
      (fields (field (name "RATING") "6V") (field (name "PACKAGE") "0402"))
      (libsource (lib "eagle-import") (part "CAP-0402"))
    )
    (comp (ref "C36")
      (value "100nF")
      (footprint "eagle-import:C0402K")
      (fields (field (name "RATING") "6V") (field (name "PACKAGE") "0402"))
      (libsource (lib "eagle-import") (part "CAP-0402"))
    )
    (comp (ref "C37")
      (value "100nF")
      (footprint "eagle-import:C0402K")
      (fields (field (name "RATING") "6V") (field (name "PACKAGE") "0402"))
      (libsource (lib "eagle-import") (part "CAP-0402"))
    )
    (comp (ref "C38")
      (value "100nF")
      (footprint "eagle-import:C0402K")
      (fields (field (name "RATING") "6V") (field (name "PACKAGE") "0402"))
      (libsource (lib "eagle-import") (part "CAP-0402"))
    )
    (comp (ref "C39")
      (value "100nF")
      (footprint "eagle-import:C0402K")
      (fields (field (name "RATING") "6V") (field (name "PACKAGE") "0402"))
      (libsource (lib "eagle-import") (part "CAP-0402"))
    )
    (comp (ref "C40")
      (value "100nF")
      (footprint "eagle-import:C0402K")
      (fields (field (name "RATING") "6V") (field (name "PACKAGE") "0402"))
      (libsource (lib "eagle-import") (part "CAP-0402"))
    )
    (comp (ref "C41")
      (value "100nF")
      (footprint "eagle-import:C0402K")
      (fields (field (name "RATING") "6V") (field (name "PACKAGE") "0402"))
      (libsource (lib "eagle-import") (part "CAP-0402"))
    )
    (comp (ref "C42")
      (value "100nF")
      (footprint "eagle-import:C0402K")
      (fields (field (name "RATING") "6V") (field (name "PACKAGE") "0402"))
      (libsource (lib "eagle-import") (part "CAP-0402"))
    )
    (comp (ref "U2")
      (value "MT48LC16M16A2")
      (footprint "eagle-import:TSOP54-400")
      (libsource (lib "eagle-import") (part "MT48LC16M16A2"))
    )
    (comp (ref "U3")
      (value "MT48LC16M16A2")
      (footprint "eagle-import:TSOP54-400")
      (libsource (lib "eagle-import") (part "MT48LC16M16A2"))
    )
    (comp (ref "C63")
      (value "100nF")
      (footprint "eagle-import:C0402K")
      (fields (field (name "RATING") "6V") (field (name "PACKAGE") "0402"))
      (libsource (lib "eagle-import") (part "CAP-0402"))
    )
    (comp (ref "CON2")
      (value "microSD")
      (footprint "eagle-import:112J")
      (libsource (lib "eagle-import") (part "112J-TXAR"))
    )
    (comp (ref "R23")
      (value "47k")
      (footprint "eagle-import:R0402")
      (libsource (lib "eagle-import") (part "R-EU_R0402"))
    )
    (comp (ref "R31")
      (value "47k")
      (footprint "eagle-import:R0402")
      (libsource (lib "eagle-import") (part "R-EU_R0402"))
    )
    (comp (ref "R32")
      (value "47k")
      (footprint "eagle-import:R0402")
      (libsource (lib "eagle-import") (part "R-EU_R0402"))
    )
    (comp (ref "R34")
      (value "47k")
      (footprint "eagle-import:R0402")
      (libsource (lib "eagle-import") (part "R-EU_R0402"))
    )
    (comp (ref "R35")
      (value "47k")
      (footprint "eagle-import:R0402")
      (libsource (lib "eagle-import") (part "R-EU_R0402"))
    )
  )
  (nets
    (net (code "97") (name "+1V8") (class "Default")
      (node (ref "+1V8") (pin "TP") (pinfunction "TP_TP") (pintype "input"))
      (node (ref "C13") (pin "1") (pinfunction "1_1") (pintype "passive"))
      (node (ref "C14") (pin "1") (pinfunction "1_1") (pintype "passive"))
      (node (ref "C15") (pin "1") (pinfunction "1_1") (pintype "passive"))
      (node (ref "C16") (pin "1") (pinfunction "1_1") (pintype "passive"))
      (node (ref "C17") (pin "1") (pinfunction "1_1") (pintype "passive"))
      (node (ref "C18") (pin "1") (pinfunction "1_1") (pintype "passive"))
      (node (ref "C19") (pin "1") (pinfunction "1_1") (pintype "passive"))
      (node (ref "C20") (pin "1") (pinfunction "1_1") (pintype "passive"))
      (node (ref "C60") (pin "1") (pinfunction "1_1") (pintype "passive"))
      (node (ref "C61") (pin "1") (pinfunction "1_1") (pintype "passive"))
      (node (ref "L2") (pin "2") (pinfunction "2_2") (pintype "passive"))
      (node (ref "R18") (pin "2") (pinfunction "2_2") (pintype "passive"))
      (node (ref "U1") (pin "116") (pinfunction "VDDCORE3_116") (pintype "power_in"))
      (node (ref "U1") (pin "152") (pinfunction "VDDCORE4_152") (pintype "power_in"))
      (node (ref "U1") (pin "188") (pinfunction "VDDCORE5_188") (pintype "power_in"))
      (node (ref "U1") (pin "19") (pinfunction "VDDCORE1_19") (pintype "power_in"))
      (node (ref "U1") (pin "28") (pinfunction "VDDPLL1_28") (pintype "power_in"))
      (node (ref "U1") (pin "33") (pinfunction "VDDOSC_33") (pintype "power_in"))
      (node (ref "U1") (pin "37") (pinfunction "VDDPLL2_37") (pintype "power_in"))
      (node (ref "U1") (pin "62") (pinfunction "VDDCORE2_62") (pintype "power_in"))
    )
    (net (code "98") (name "+3V3") (class "Default")
      (node (ref "+3V3") (pin "TP") (pinfunction "TP_TP") (pintype "input"))
      (node (ref "C1") (pin "1") (pinfunction "1_1") (pintype "passive"))
      (node (ref "C10") (pin "1") (pinfunction "1_1") (pintype "passive"))
      (node (ref "C11") (pin "1") (pinfunction "1_1") (pintype "passive"))
      (node (ref "C12") (pin "1") (pinfunction "1_1") (pintype "passive"))
      (node (ref "C2") (pin "1") (pinfunction "1_1") (pintype "passive"))
      (node (ref "C29") (pin "1") (pinfunction "1_1") (pintype "passive"))
      (node (ref "C3") (pin "1") (pinfunction "1_1") (pintype "passive"))
      (node (ref "C30") (pin "1") (pinfunction "1_1") (pintype "passive"))
      (node (ref "C31") (pin "1") (pinfunction "1_1") (pintype "passive"))
      (node (ref "C32") (pin "1") (pinfunction "1_1") (pintype "passive"))
      (node (ref "C33") (pin "1") (pinfunction "1_1") (pintype "passive"))
      (node (ref "C34") (pin "1") (pinfunction "1_1") (pintype "passive"))
      (node (ref "C35") (pin "1") (pinfunction "1_1") (pintype "passive"))
      (node (ref "C36") (pin "1") (pinfunction "1_1") (pintype "passive"))
      (node (ref "C37") (pin "1") (pinfunction "1_1") (pintype "passive"))
      (node (ref "C38") (pin "1") (pinfunction "1_1") (pintype "passive"))
      (node (ref "C39") (pin "1") (pinfunction "1_1") (pintype "passive"))
      (node (ref "C4") (pin "1") (pinfunction "1_1") (pintype "passive"))
      (node (ref "C40") (pin "1") (pinfunction "1_1") (pintype "passive"))
      (node (ref "C41") (pin "1") (pinfunction "1_1") (pintype "passive"))
      (node (ref "C42") (pin "1") (pinfunction "1_1") (pintype "passive"))
      (node (ref "C5") (pin "1") (pinfunction "1_1") (pintype "passive"))
      (node (ref "C58") (pin "1") (pinfunction "1_1") (pintype "passive"))
      (node (ref "C59") (pin "1") (pinfunction "1_1") (pintype "passive"))
      (node (ref "C6") (pin "1") (pinfunction "1_1") (pintype "passive"))
      (node (ref "C62") (pin "1") (pinfunction "1_1") (pintype "passive"))
      (node (ref "C63") (pin "1") (pinfunction "1_1") (pintype "passive"))
      (node (ref "C64") (pin "1") (pinfunction "1_1") (pintype "passive"))
      (node (ref "C65") (pin "1") (pinfunction "1_1") (pintype "passive"))
      (node (ref "C7") (pin "1") (pinfunction "1_1") (pintype "passive"))
      (node (ref "C8") (pin "1") (pinfunction "1_1") (pintype "passive"))
      (node (ref "C9") (pin "1") (pinfunction "1_1") (pintype "passive"))
      (node (ref "CON2") (pin "P$4") (pinfunction "VDD_P$4") (pintype "input"))
      (node (ref "L1") (pin "2") (pinfunction "2_2") (pintype "passive"))
      (node (ref "LED1") (pin "2") (pinfunction "2_2") (pintype "passive"))
      (node (ref "R16") (pin "2") (pinfunction "2_2") (pintype "passive"))
      (node (ref "R23") (pin "1") (pinfunction "1_1") (pintype "passive"))
      (node (ref "R24") (pin "2") (pinfunction "2_2") (pintype "passive"))
      (node (ref "R25") (pin "2") (pinfunction "2_2") (pintype "passive"))
      (node (ref "R26") (pin "2") (pinfunction "2_2") (pintype "passive"))
      (node (ref "R27") (pin "2") (pinfunction "2_2") (pintype "passive"))
      (node (ref "R28") (pin "2") (pinfunction "2_2") (pintype "passive"))
      (node (ref "R29") (pin "2") (pinfunction "2_2") (pintype "passive"))
      (node (ref "R3") (pin "1") (pinfunction "1_1") (pintype "passive"))
      (node (ref "R30") (pin "2") (pinfunction "2_2") (pintype "passive"))
      (node (ref "R31") (pin "1") (pinfunction "1_1") (pintype "passive"))
      (node (ref "R32") (pin "1") (pinfunction "1_1") (pintype "passive"))
      (node (ref "R34") (pin "1") (pinfunction "1_1") (pintype "passive"))
      (node (ref "R35") (pin "1") (pinfunction "1_1") (pintype "passive"))
      (node (ref "R4") (pin "1") (pinfunction "1_1") (pintype "passive"))
      (node (ref "R8") (pin "2") (pinfunction "2_2") (pintype "passive"))
      (node (ref "SV1") (pin "3") (pinfunction "3_3") (pintype "passive"))
      (node (ref "T1") (pin "C") (pinfunction "C_C") (pintype "passive"))
      (node (ref "U1") (pin "111") (pinfunction "VDDIOP5_111") (pintype "power_in"))
      (node (ref "U1") (pin "129") (pinfunction "VDDIOP6_129") (pintype "power_in"))
      (node (ref "U1") (pin "131") (pinfunction "VDDIOM3_131") (pintype "power_in"))
      (node (ref "U1") (pin "146") (pinfunction "VDDIOM4_146") (pintype "power_in"))
      (node (ref "U1") (pin "164") (pinfunction "VDDIOM5_164") (pintype "power_in"))
      (node (ref "U1") (pin "183") (pinfunction "VDDIOM6_183") (pintype "power_in"))
      (node (ref "U1") (pin "199") (pinfunction "VDDIOM7_199") (pintype "power_in"))
      (node (ref "U1") (pin "26") (pinfunction "VDDIOM2_26") (pintype "power_in"))
      (node (ref "U1") (pin "40") (pinfunction "VDDIOP1_40") (pintype "power_in"))
      (node (ref "U1") (pin "56") (pinfunction "VDDIOP2_56") (pintype "power_in"))
      (node (ref "U1") (pin "7") (pinfunction "VDDIOM1_7") (pintype "power_in"))
      (node (ref "U1") (pin "75") (pinfunction "VDDIOP3_75") (pintype "power_in"))
      (node (ref "U1") (pin "93") (pinfunction "VDDIOP4_93") (pintype "power_in"))
      (node (ref "U2") (pin "1") (pinfunction "VDD_1") (pintype "power_in"))
      (node (ref "U2") (pin "14") (pinfunction "VDD_14") (pintype "power_in"))
      (node (ref "U2") (pin "27") (pinfunction "VDD_27") (pintype "power_in"))
      (node (ref "U2") (pin "3") (pinfunction "VDDQ_3") (pintype "power_in"))
      (node (ref "U2") (pin "43") (pinfunction "VDDQ_43") (pintype "power_in"))
      (node (ref "U2") (pin "49") (pinfunction "VDDQ_49") (pintype "power_in"))
      (node (ref "U2") (pin "9") (pinfunction "VDDQ_9") (pintype "power_in"))
      (node (ref "U3") (pin "1") (pinfunction "VDD_1") (pintype "power_in"))
      (node (ref "U3") (pin "14") (pinfunction "VDD_14") (pintype "power_in"))
      (node (ref "U3") (pin "27") (pinfunction "VDD_27") (pintype "power_in"))
      (node (ref "U3") (pin "3") (pinfunction "VDDQ_3") (pintype "power_in"))
      (node (ref "U3") (pin "43") (pinfunction "VDDQ_43") (pintype "power_in"))
      (node (ref "U3") (pin "49") (pinfunction "VDDQ_49") (pintype "power_in"))
      (node (ref "U3") (pin "9") (pinfunction "VDDQ_9") (pintype "power_in"))
      (node (ref "U6") (pin "3") (pinfunction "VCC_3") (pintype "bidirectional"))
      (node (ref "U7") (pin "6") (pinfunction "VCC_6") (pintype "power_in"))
    )
    (net (code "99") (name "+5V") (class "Default")
      (node (ref "C43") (pin "1") (pinfunction "1_1") (pintype "passive"))
      (node (ref "C46") (pin "1") (pinfunction "1_1") (pintype "passive"))
      (node (ref "C53") (pin "1") (pinfunction "1_1") (pintype "passive"))
      (node (ref "C54") (pin "1") (pinfunction "1_1") (pintype "passive"))
      (node (ref "C55") (pin "1") (pinfunction "1_1") (pintype "passive"))
      (node (ref "IC4") (pin "7") (pinfunction "OUT_7") (pintype "bidirectional"))
      (node (ref "J1") (pin "2") (pinfunction "2_2") (pintype "passive"))
      (node (ref "J2") (pin "1") (pinfunction "1_1") (pintype "passive"))
      (node (ref "U4") (pin "3") (pinfunction "VIN_3") (pintype "bidirectional"))
      (node (ref "U4") (pin "5") (pinfunction "EN_5") (pintype "bidirectional"))
      (node (ref "U5") (pin "3") (pinfunction "VIN_3") (pintype "bidirectional"))
      (node (ref "U5") (pin "5") (pinfunction "EN_5") (pintype "bidirectional"))
    )
    (net (code "103") (name "31") (class "Default")
      (node (ref "SV1") (pin "31") (pinfunction "31_31") (pintype "passive"))
      (node (ref "U1") (pin "24") (pinfunction "PC5_24") (pintype "bidirectional"))
    )
    (net (code "104") (name "32") (class "Default")
      (node (ref "SV1") (pin "32") (pinfunction "32_32") (pintype "passive"))
      (node (ref "U1") (pin "23") (pinfunction "PC4_23") (pintype "bidirectional"))
    )
    (net (code "105") (name "33") (class "Default")
      (node (ref "SV1") (pin "33") (pinfunction "33_33") (pintype "passive"))
      (node (ref "U1") (pin "22") (pinfunction "PC3_22") (pintype "bidirectional"))
    )
    (net (code "106") (name "34") (class "Default")
      (node (ref "SV1") (pin "34") (pinfunction "34_34") (pintype "passive"))
      (node (ref "U1") (pin "21") (pinfunction "PC2_21") (pintype "bidirectional"))
    )
    (net (code "107") (name "35") (class "Default")
      (node (ref "SV1") (pin "35") (pinfunction "35_35") (pintype "passive"))
      (node (ref "U1") (pin "18") (pinfunction "PC1_18") (pintype "bidirectional"))
    )
    (net (code "108") (name "36") (class "Default")
      (node (ref "SV1") (pin "36") (pinfunction "36_36") (pintype "passive"))
      (node (ref "U1") (pin "17") (pinfunction "PC0_17") (pintype "bidirectional"))
    )
    (net (code "109") (name "A23") (class "Default")
      (node (ref "U1") (pin "161") (pinfunction "PC7_161") (pintype "bidirectional"))
    )
    (net (code "110") (name "ADDR0") (class "Default")
      (node (ref "U1") (pin "133") (pinfunction "A0/NBS0_133") (pintype "output"))
      (node (ref "U2") (pin "15") (pinfunction "DQML_15") (pintype "input"))
    )
    (net (code "111") (name "ADDR1") (class "Default")
      (node (ref "U1") (pin "134") (pinfunction "A1/NBS2/NWR2_134") (pintype "output"))
      (node (ref "U3") (pin "15") (pinfunction "DQML_15") (pintype "input"))
    )
    (net (code "112") (name "ADDR2") (class "Default")
      (node (ref "U1") (pin "135") (pinfunction "A2_135") (pintype "output"))
      (node (ref "U2") (pin "23") (pinfunction "A0_23") (pintype "input"))
      (node (ref "U3") (pin "23") (pinfunction "A0_23") (pintype "input"))
    )
    (net (code "113") (name "ADDR3") (class "Default")
      (node (ref "U1") (pin "136") (pinfunction "A3_136") (pintype "output"))
      (node (ref "U2") (pin "24") (pinfunction "A1_24") (pintype "input"))
      (node (ref "U3") (pin "24") (pinfunction "A1_24") (pintype "input"))
    )
    (net (code "114") (name "ADDR4") (class "Default")
      (node (ref "U1") (pin "137") (pinfunction "A4_137") (pintype "output"))
      (node (ref "U2") (pin "25") (pinfunction "A2_25") (pintype "input"))
      (node (ref "U3") (pin "25") (pinfunction "A2_25") (pintype "input"))
    )
    (net (code "115") (name "ADDR5") (class "Default")
      (node (ref "U1") (pin "138") (pinfunction "A5_138") (pintype "output"))
      (node (ref "U2") (pin "26") (pinfunction "A3_26") (pintype "input"))
      (node (ref "U3") (pin "26") (pinfunction "A3_26") (pintype "input"))
    )
    (net (code "116") (name "ADDR6") (class "Default")
      (node (ref "U1") (pin "139") (pinfunction "A6_139") (pintype "output"))
      (node (ref "U2") (pin "29") (pinfunction "A4_29") (pintype "input"))
      (node (ref "U3") (pin "29") (pinfunction "A4_29") (pintype "input"))
    )
    (net (code "117") (name "ADDR7") (class "Default")
      (node (ref "U1") (pin "140") (pinfunction "A7_140") (pintype "output"))
      (node (ref "U2") (pin "30") (pinfunction "A5_30") (pintype "input"))
      (node (ref "U3") (pin "30") (pinfunction "A5_30") (pintype "input"))
    )
    (net (code "118") (name "ADDR8") (class "Default")
      (node (ref "U1") (pin "141") (pinfunction "A8_141") (pintype "output"))
      (node (ref "U2") (pin "31") (pinfunction "A6_31") (pintype "input"))
      (node (ref "U3") (pin "31") (pinfunction "A6_31") (pintype "input"))
    )
    (net (code "119") (name "ADDR9") (class "Default")
      (node (ref "U1") (pin "142") (pinfunction "A9_142") (pintype "output"))
      (node (ref "U2") (pin "32") (pinfunction "A7_32") (pintype "input"))
      (node (ref "U3") (pin "32") (pinfunction "A7_32") (pintype "input"))
    )
    (net (code "120") (name "ADDR10") (class "Default")
      (node (ref "U1") (pin "143") (pinfunction "A10_143") (pintype "output"))
      (node (ref "U2") (pin "33") (pinfunction "A8_33") (pintype "input"))
      (node (ref "U3") (pin "33") (pinfunction "A8_33") (pintype "input"))
    )
    (net (code "121") (name "ADDR11") (class "Default")
      (node (ref "U1") (pin "145") (pinfunction "A11_145") (pintype "output"))
      (node (ref "U2") (pin "34") (pinfunction "A9_34") (pintype "input"))
      (node (ref "U3") (pin "34") (pinfunction "A9_34") (pintype "input"))
    )
    (net (code "122") (name "ADDR13") (class "Default")
      (node (ref "U1") (pin "149") (pinfunction "A13_149") (pintype "output"))
      (node (ref "U2") (pin "35") (pinfunction "A11_35") (pintype "input"))
      (node (ref "U3") (pin "35") (pinfunction "A11_35") (pintype "input"))
    )
    (net (code "123") (name "ADDR14") (class "Default")
      (node (ref "U1") (pin "150") (pinfunction "A14_150") (pintype "output"))
      (node (ref "U2") (pin "36") (pinfunction "A12_36") (pintype "input"))
      (node (ref "U3") (pin "36") (pinfunction "A12_36") (pintype "input"))
    )
    (net (code "124") (name "ADDR16") (class "Default")
      (node (ref "U1") (pin "154") (pinfunction "A16/BA0_154") (pintype "output"))
      (node (ref "U2") (pin "20") (pinfunction "BA0_20") (pintype "input"))
      (node (ref "U3") (pin "20") (pinfunction "BA0_20") (pintype "input"))
    )
    (net (code "125") (name "ADDR17") (class "Default")
      (node (ref "U1") (pin "155") (pinfunction "A17/BA1_155") (pintype "output"))
      (node (ref "U2") (pin "21") (pinfunction "BA1_21") (pintype "input"))
      (node (ref "U3") (pin "21") (pinfunction "BA1_21") (pintype "input"))
    )
    (net (code "126") (name "BMS") (class "Default")
      (node (ref "DTX") (pin "TP") (pinfunction "TP_TP") (pintype "input"))
      (node (ref "R25") (pin "1") (pinfunction "1_1") (pintype "passive"))
      (node (ref "U1") (pin "79") (pinfunction "PA31/BMS_79") (pintype "bidirectional"))
    )
    (net (code "127") (name "CAN_RX") (class "Default")
      (node (ref "SV1") (pin "30") (pinfunction "30_30") (pintype "passive"))
    )
    (net (code "128") (name "CAN_TX") (class "Default")
      (node (ref "SV1") (pin "29") (pinfunction "29_29") (pintype "passive"))
    )
    (net (code "129") (name "CAPE_EN1") (class "Default")
      (node (ref "SV1") (pin "13") (pinfunction "13_13") (pintype "passive"))
      (node (ref "U1") (pin "80") (pinfunction "PB0_80") (pintype "bidirectional"))
    )
    (net (code "130") (name "CAPE_EN2") (class "Default")
      (node (ref "SV1") (pin "14") (pinfunction "14_14") (pintype "passive"))
      (node (ref "U1") (pin "81") (pinfunction "PB1_81") (pintype "bidirectional"))
    )
    (net (code "131") (name "CAS") (class "Default")
      (node (ref "U1") (pin "177") (pinfunction "CAS_177") (pintype "bidirectional"))
      (node (ref "U2") (pin "17") (pinfunction "~{CAS}_17") (pintype "input"))
      (node (ref "U3") (pin "17") (pinfunction "~{CAS}_17") (pintype "input"))
    )
    (net (code "132") (name "CFCS") (class "Default")
      (node (ref "U1") (pin "11") (pinfunction "PC10_11") (pintype "bidirectional"))
    )
    (net (code "133") (name "CFIOR_NBS1_NWR1") (class "Default")
      (node (ref "U1") (pin "172") (pinfunction "NWR1/NBS1/CFIOR_172") (pintype "bidirectional"))
      (node (ref "U2") (pin "39") (pinfunction "DQMH_39") (pintype "input"))
    )
    (net (code "134") (name "CFIOW_NBS3_NWR3") (class "Default")
      (node (ref "U1") (pin "173") (pinfunction "NWR3/NBS3/CFIOW_173") (pintype "bidirectional"))
      (node (ref "U3") (pin "39") (pinfunction "DQMH_39") (pintype "input"))
    )
    (net (code "135") (name "CFRNW") (class "Default")
      (node (ref "U1") (pin "163") (pinfunction "PC9_163") (pintype "bidirectional"))
    )
    (net (code "136") (name "DATA0") (class "Default")
      (node (ref "U1") (pin "179") (pinfunction "D0_179") (pintype "bidirectional"))
      (node (ref "U2") (pin "2") (pinfunction "DQ0_2") (pintype "tri_state"))
    )
    (net (code "137") (name "DATA1") (class "Default")
      (node (ref "U1") (pin "180") (pinfunction "D1_180") (pintype "bidirectional"))
      (node (ref "U2") (pin "4") (pinfunction "DQ1_4") (pintype "tri_state"))
    )
    (net (code "138") (name "DATA2") (class "Default")
      (node (ref "U1") (pin "181") (pinfunction "D2_181") (pintype "bidirectional"))
      (node (ref "U2") (pin "5") (pinfunction "DQ2_5") (pintype "tri_state"))
    )
    (net (code "139") (name "DATA3") (class "Default")
      (node (ref "U1") (pin "182") (pinfunction "D3_182") (pintype "bidirectional"))
      (node (ref "U2") (pin "7") (pinfunction "DQ3_7") (pintype "tri_state"))
    )
    (net (code "140") (name "DATA4") (class "Default")
      (node (ref "U1") (pin "185") (pinfunction "D4_185") (pintype "bidirectional"))
      (node (ref "U2") (pin "8") (pinfunction "DQ4_8") (pintype "tri_state"))
    )
    (net (code "141") (name "DATA5") (class "Default")
      (node (ref "U1") (pin "186") (pinfunction "D5_186") (pintype "bidirectional"))
      (node (ref "U2") (pin "10") (pinfunction "DQ5_10") (pintype "tri_state"))
    )
    (net (code "142") (name "DATA6") (class "Default")
      (node (ref "U1") (pin "187") (pinfunction "D6_187") (pintype "bidirectional"))
      (node (ref "U2") (pin "11") (pinfunction "DQ6_11") (pintype "tri_state"))
    )
    (net (code "143") (name "DATA7") (class "Default")
      (node (ref "U1") (pin "190") (pinfunction "D7_190") (pintype "bidirectional"))
      (node (ref "U2") (pin "13") (pinfunction "DQ7_13") (pintype "tri_state"))
    )
    (net (code "144") (name "DATA8") (class "Default")
      (node (ref "U1") (pin "191") (pinfunction "D8_191") (pintype "bidirectional"))
      (node (ref "U2") (pin "42") (pinfunction "DQ8_42") (pintype "tri_state"))
    )
    (net (code "145") (name "DATA9") (class "Default")
      (node (ref "U1") (pin "192") (pinfunction "D9_192") (pintype "bidirectional"))
      (node (ref "U2") (pin "44") (pinfunction "DQ9_44") (pintype "tri_state"))
    )
    (net (code "146") (name "DATA10") (class "Default")
      (node (ref "U1") (pin "193") (pinfunction "D10_193") (pintype "bidirectional"))
      (node (ref "U2") (pin "45") (pinfunction "DQ10_45") (pintype "tri_state"))
    )
    (net (code "147") (name "DATA11") (class "Default")
      (node (ref "U1") (pin "194") (pinfunction "D11_194") (pintype "bidirectional"))
      (node (ref "U2") (pin "47") (pinfunction "DQ11_47") (pintype "tri_state"))
    )
    (net (code "148") (name "DATA12") (class "Default")
      (node (ref "U1") (pin "195") (pinfunction "D12_195") (pintype "bidirectional"))
      (node (ref "U2") (pin "48") (pinfunction "DQ12_48") (pintype "tri_state"))
    )
    (net (code "149") (name "DATA13") (class "Default")
      (node (ref "U1") (pin "196") (pinfunction "D13_196") (pintype "bidirectional"))
      (node (ref "U2") (pin "50") (pinfunction "DQ13_50") (pintype "tri_state"))
    )
    (net (code "150") (name "DATA14") (class "Default")
      (node (ref "U1") (pin "197") (pinfunction "D14_197") (pintype "bidirectional"))
      (node (ref "U2") (pin "51") (pinfunction "DQ14_51") (pintype "tri_state"))
    )
    (net (code "151") (name "DATA15") (class "Default")
      (node (ref "U1") (pin "198") (pinfunction "D15_198") (pintype "bidirectional"))
      (node (ref "U2") (pin "53") (pinfunction "DQ15_53") (pintype "tri_state"))
    )
    (net (code "152") (name "DATA16") (class "Default")
      (node (ref "U1") (pin "201") (pinfunction "PC16_201") (pintype "bidirectional"))
      (node (ref "U3") (pin "2") (pinfunction "DQ0_2") (pintype "tri_state"))
    )
    (net (code "153") (name "DATA17") (class "Default")
      (node (ref "U1") (pin "202") (pinfunction "PC17_202") (pintype "bidirectional"))
      (node (ref "U3") (pin "4") (pinfunction "DQ1_4") (pintype "tri_state"))
    )
    (net (code "154") (name "DATA18") (class "Default")
      (node (ref "U1") (pin "203") (pinfunction "PC18_203") (pintype "bidirectional"))
      (node (ref "U3") (pin "5") (pinfunction "DQ2_5") (pintype "tri_state"))
    )
    (net (code "155") (name "DATA19") (class "Default")
      (node (ref "U1") (pin "204") (pinfunction "PC19_204") (pintype "bidirectional"))
      (node (ref "U3") (pin "7") (pinfunction "DQ3_7") (pintype "tri_state"))
    )
    (net (code "156") (name "DATA20") (class "Default")
      (node (ref "U1") (pin "205") (pinfunction "PC20_205") (pintype "bidirectional"))
      (node (ref "U3") (pin "8") (pinfunction "DQ4_8") (pintype "tri_state"))
    )
    (net (code "157") (name "DATA21") (class "Default")
      (node (ref "U1") (pin "206") (pinfunction "PC21_206") (pintype "bidirectional"))
      (node (ref "U3") (pin "10") (pinfunction "DQ5_10") (pintype "tri_state"))
    )
    (net (code "158") (name "DATA22") (class "Default")
      (node (ref "U1") (pin "207") (pinfunction "PC22_207") (pintype "bidirectional"))
      (node (ref "U3") (pin "11") (pinfunction "DQ6_11") (pintype "tri_state"))
    )
    (net (code "159") (name "DATA23") (class "Default")
      (node (ref "U1") (pin "208") (pinfunction "PC23_208") (pintype "bidirectional"))
      (node (ref "U3") (pin "13") (pinfunction "DQ7_13") (pintype "tri_state"))
    )
    (net (code "160") (name "DATA24") (class "Default")
      (node (ref "U1") (pin "1") (pinfunction "PC24_1") (pintype "bidirectional"))
      (node (ref "U3") (pin "42") (pinfunction "DQ8_42") (pintype "tri_state"))
    )
    (net (code "161") (name "DATA25") (class "Default")
      (node (ref "U1") (pin "2") (pinfunction "PC25_2") (pintype "bidirectional"))
      (node (ref "U3") (pin "44") (pinfunction "DQ9_44") (pintype "tri_state"))
    )
    (net (code "162") (name "DATA26") (class "Default")
      (node (ref "U1") (pin "3") (pinfunction "PC26_3") (pintype "bidirectional"))
      (node (ref "U3") (pin "45") (pinfunction "DQ10_45") (pintype "tri_state"))
    )
    (net (code "163") (name "DATA27") (class "Default")
      (node (ref "U1") (pin "4") (pinfunction "PC27_4") (pintype "bidirectional"))
      (node (ref "U3") (pin "47") (pinfunction "DQ11_47") (pintype "tri_state"))
    )
    (net (code "164") (name "DATA28") (class "Default")
      (node (ref "U1") (pin "5") (pinfunction "PC28_5") (pintype "bidirectional"))
      (node (ref "U3") (pin "48") (pinfunction "DQ12_48") (pintype "tri_state"))
    )
    (net (code "165") (name "DATA29") (class "Default")
      (node (ref "U1") (pin "6") (pinfunction "PC29_6") (pintype "bidirectional"))
      (node (ref "U3") (pin "50") (pinfunction "DQ13_50") (pintype "tri_state"))
    )
    (net (code "166") (name "DATA30") (class "Default")
      (node (ref "U1") (pin "9") (pinfunction "PC30_9") (pintype "bidirectional"))
      (node (ref "U3") (pin "51") (pinfunction "DQ14_51") (pintype "tri_state"))
    )
    (net (code "167") (name "DATA31") (class "Default")
      (node (ref "U1") (pin "10") (pinfunction "PC31_10") (pintype "bidirectional"))
      (node (ref "U3") (pin "53") (pinfunction "DQ15_53") (pintype "tri_state"))
    )
    (net (code "183") (name "FIQ") (class "Default")
      (node (ref "SV1") (pin "19") (pinfunction "19_19") (pintype "passive"))
      (node (ref "U1") (pin "123") (pinfunction "PB28_123") (pintype "bidirectional"))
    )
    (net (code "184") (name "GND") (class "Default")
      (node (ref "C1") (pin "2") (pinfunction "2_2") (pintype "passive"))
      (node (ref "C10") (pin "2") (pinfunction "2_2") (pintype "passive"))
      (node (ref "C11") (pin "2") (pinfunction "2_2") (pintype "passive"))
      (node (ref "C12") (pin "2") (pinfunction "2_2") (pintype "passive"))
      (node (ref "C13") (pin "2") (pinfunction "2_2") (pintype "passive"))
      (node (ref "C14") (pin "2") (pinfunction "2_2") (pintype "passive"))
      (node (ref "C15") (pin "2") (pinfunction "2_2") (pintype "passive"))
      (node (ref "C16") (pin "2") (pinfunction "2_2") (pintype "passive"))
      (node (ref "C17") (pin "2") (pinfunction "2_2") (pintype "passive"))
      (node (ref "C18") (pin "2") (pinfunction "2_2") (pintype "passive"))
      (node (ref "C19") (pin "2") (pinfunction "2_2") (pintype "passive"))
      (node (ref "C2") (pin "2") (pinfunction "2_2") (pintype "passive"))
      (node (ref "C20") (pin "2") (pinfunction "2_2") (pintype "passive"))
      (node (ref "C21") (pin "2") (pinfunction "2_2") (pintype "passive"))
      (node (ref "C22") (pin "2") (pinfunction "2_2") (pintype "passive"))
      (node (ref "C23") (pin "2") (pinfunction "2_2") (pintype "passive"))
      (node (ref "C24") (pin "2") (pinfunction "2_2") (pintype "passive"))
      (node (ref "C25") (pin "2") (pinfunction "2_2") (pintype "passive"))
      (node (ref "C26") (pin "2") (pinfunction "2_2") (pintype "passive"))
      (node (ref "C27") (pin "2") (pinfunction "2_2") (pintype "passive"))
      (node (ref "C28") (pin "2") (pinfunction "2_2") (pintype "passive"))
      (node (ref "C29") (pin "2") (pinfunction "2_2") (pintype "passive"))
      (node (ref "C3") (pin "2") (pinfunction "2_2") (pintype "passive"))
      (node (ref "C30") (pin "2") (pinfunction "2_2") (pintype "passive"))
      (node (ref "C31") (pin "2") (pinfunction "2_2") (pintype "passive"))
      (node (ref "C32") (pin "2") (pinfunction "2_2") (pintype "passive"))
      (node (ref "C33") (pin "2") (pinfunction "2_2") (pintype "passive"))
      (node (ref "C34") (pin "2") (pinfunction "2_2") (pintype "passive"))
      (node (ref "C35") (pin "2") (pinfunction "2_2") (pintype "passive"))
      (node (ref "C36") (pin "2") (pinfunction "2_2") (pintype "passive"))
      (node (ref "C37") (pin "2") (pinfunction "2_2") (pintype "passive"))
      (node (ref "C38") (pin "2") (pinfunction "2_2") (pintype "passive"))
      (node (ref "C39") (pin "2") (pinfunction "2_2") (pintype "passive"))
      (node (ref "C4") (pin "2") (pinfunction "2_2") (pintype "passive"))
      (node (ref "C40") (pin "2") (pinfunction "2_2") (pintype "passive"))
      (node (ref "C41") (pin "2") (pinfunction "2_2") (pintype "passive"))
      (node (ref "C42") (pin "2") (pinfunction "2_2") (pintype "passive"))
      (node (ref "C43") (pin "2") (pinfunction "2_2") (pintype "passive"))
      (node (ref "C44") (pin "2") (pinfunction "2_2") (pintype "passive"))
      (node (ref "C45") (pin "2") (pinfunction "2_2") (pintype "passive"))
      (node (ref "C46") (pin "2") (pinfunction "2_2") (pintype "passive"))
      (node (ref "C47") (pin "2") (pinfunction "2_2") (pintype "passive"))
      (node (ref "C48") (pin "2") (pinfunction "2_2") (pintype "passive"))
      (node (ref "C49") (pin "2") (pinfunction "2_2") (pintype "passive"))
      (node (ref "C5") (pin "2") (pinfunction "2_2") (pintype "passive"))
      (node (ref "C51") (pin "2") (pinfunction "2_2") (pintype "passive"))
      (node (ref "C52") (pin "2") (pinfunction "2_2") (pintype "passive"))
      (node (ref "C53") (pin "2") (pinfunction "2_2") (pintype "passive"))
      (node (ref "C54") (pin "2") (pinfunction "2_2") (pintype "passive"))
      (node (ref "C55") (pin "2") (pinfunction "2_2") (pintype "passive"))
      (node (ref "C58") (pin "2") (pinfunction "2_2") (pintype "passive"))
      (node (ref "C59") (pin "2") (pinfunction "2_2") (pintype "passive"))
      (node (ref "C6") (pin "2") (pinfunction "2_2") (pintype "passive"))
      (node (ref "C60") (pin "2") (pinfunction "2_2") (pintype "passive"))
      (node (ref "C61") (pin "2") (pinfunction "2_2") (pintype "passive"))
      (node (ref "C62") (pin "2") (pinfunction "2_2") (pintype "passive"))
      (node (ref "C63") (pin "2") (pinfunction "2_2") (pintype "passive"))
      (node (ref "C64") (pin "2") (pinfunction "2_2") (pintype "passive"))
      (node (ref "C65") (pin "2") (pinfunction "2_2") (pintype "passive"))
      (node (ref "C7") (pin "2") (pinfunction "2_2") (pintype "passive"))
      (node (ref "C8") (pin "2") (pinfunction "2_2") (pintype "passive"))
      (node (ref "C9") (pin "2") (pinfunction "2_2") (pintype "passive"))
      (node (ref "CON1") (pin "5") (pinfunction "GND_5") (pintype "bidirectional"))
      (node (ref "CON1") (pin "SH1") (pinfunction "GND_SH1") (pintype "bidirectional"))
      (node (ref "CON1") (pin "SH2") (pinfunction "GND_SH2") (pintype "bidirectional"))
      (node (ref "CON1") (pin "SH3") (pinfunction "GND_SH3") (pintype "bidirectional"))
      (node (ref "CON1") (pin "SH4") (pinfunction "GND_SH4") (pintype "bidirectional"))
      (node (ref "CON1") (pin "SH5") (pinfunction "GND_SH5") (pintype "bidirectional"))
      (node (ref "CON1") (pin "SH6") (pinfunction "GND_SH6") (pintype "bidirectional"))
      (node (ref "CON1") (pin "SH7") (pinfunction "GND_SH7") (pintype "bidirectional"))
      (node (ref "CON1") (pin "SH8") (pinfunction "GND_SH8") (pintype "bidirectional"))
      (node (ref "CON2") (pin "GND1") (pinfunction "GND_GND1") (pintype "power_in"))
      (node (ref "CON2") (pin "GND2") (pinfunction "GND_GND2") (pintype "power_in"))
      (node (ref "CON2") (pin "GND3") (pinfunction "GND_GND3") (pintype "power_in"))
      (node (ref "CON2") (pin "GND4") (pinfunction "GND_GND4") (pintype "power_in"))
      (node (ref "CON2") (pin "P$6") (pinfunction "VSS_P$6") (pintype "bidirectional"))
      (node (ref "GND") (pin "TP") (pinfunction "TP_TP") (pintype "input"))
      (node (ref "IC4") (pin "3") (pinfunction "3_3") (pintype "bidirectional"))
      (node (ref "IC4") (pin "5") (pinfunction "GND_5") (pintype "bidirectional"))
      (node (ref "R11") (pin "1") (pinfunction "1_1") (pintype "passive"))
      (node (ref "R12") (pin "1") (pinfunction "1_1") (pintype "passive"))
      (node (ref "R14") (pin "1") (pinfunction "1_1") (pintype "passive"))
      (node (ref "R17") (pin "2") (pinfunction "2_2") (pintype "passive"))
      (node (ref "R19") (pin "2") (pinfunction "2_2") (pintype "passive"))
      (node (ref "R36") (pin "1") (pinfunction "1_1") (pintype "passive"))
      (node (ref "SV1") (pin "1") (pinfunction "1_1") (pintype "passive"))
      (node (ref "TP1") (pin "TP") (pinfunction "TP_TP") (pintype "input"))
      (node (ref "U1") (pin "105") (pinfunction "JTAGSEL_105") (pintype "input"))
      (node (ref "U1") (pin "112") (pinfunction "GND9_112") (pintype "power_in"))
      (node (ref "U1") (pin "113") (pinfunction "TST0_113") (pintype "input"))
      (node (ref "U1") (pin "114") (pinfunction "TST1_114") (pintype "input"))
      (node (ref "U1") (pin "117") (pinfunction "GND10_117") (pintype "power_in"))
      (node (ref "U1") (pin "130") (pinfunction "GND11_130") (pintype "power_in"))
      (node (ref "U1") (pin "132") (pinfunction "GND12_132") (pintype "power_in"))
      (node (ref "U1") (pin "147") (pinfunction "GND13_147") (pintype "power_in"))
      (node (ref "U1") (pin "153") (pinfunction "GND14_153") (pintype "power_in"))
      (node (ref "U1") (pin "165") (pinfunction "GND15_165") (pintype "power_in"))
      (node (ref "U1") (pin "184") (pinfunction "GND16_184") (pintype "power_in"))
      (node (ref "U1") (pin "189") (pinfunction "GND17_189") (pintype "power_in"))
      (node (ref "U1") (pin "20") (pinfunction "GND2_20") (pintype "power_in"))
      (node (ref "U1") (pin "200") (pinfunction "GND18_200") (pintype "power_in"))
      (node (ref "U1") (pin "27") (pinfunction "GND3_27") (pintype "power_in"))
      (node (ref "U1") (pin "30") (pinfunction "GNDPLL1_30") (pintype "power_in"))
      (node (ref "U1") (pin "34") (pinfunction "GNDOSC_34") (pintype "power_in"))
      (node (ref "U1") (pin "39") (pinfunction "GNDPLL2_39") (pintype "power_in"))
      (node (ref "U1") (pin "41") (pinfunction "GND4_41") (pintype "power_in"))
      (node (ref "U1") (pin "57") (pinfunction "GND5_57") (pintype "power_in"))
      (node (ref "U1") (pin "63") (pinfunction "GND6_63") (pintype "power_in"))
      (node (ref "U1") (pin "76") (pinfunction "GND7_76") (pintype "power_in"))
      (node (ref "U1") (pin "8") (pinfunction "GND1_8") (pintype "power_in"))
      (node (ref "U1") (pin "94") (pinfunction "GND8_94") (pintype "power_in"))
      (node (ref "U2") (pin "12") (pinfunction "VSSQ_12") (pintype "power_in"))
      (node (ref "U2") (pin "28") (pinfunction "VSS_28") (pintype "power_in"))
      (node (ref "U2") (pin "41") (pinfunction "VSS_41") (pintype "power_in"))
      (node (ref "U2") (pin "46") (pinfunction "VSSQ_46") (pintype "power_in"))
      (node (ref "U2") (pin "52") (pinfunction "VSSQ_52") (pintype "power_in"))
      (node (ref "U2") (pin "54") (pinfunction "VSS_54") (pintype "power_in"))
      (node (ref "U2") (pin "6") (pinfunction "VSSQ_6") (pintype "power_in"))
      (node (ref "U3") (pin "12") (pinfunction "VSSQ_12") (pintype "power_in"))
      (node (ref "U3") (pin "28") (pinfunction "VSS_28") (pintype "power_in"))
      (node (ref "U3") (pin "41") (pinfunction "VSS_41") (pintype "power_in"))
      (node (ref "U3") (pin "46") (pinfunction "VSSQ_46") (pintype "power_in"))
      (node (ref "U3") (pin "52") (pinfunction "VSSQ_52") (pintype "power_in"))
      (node (ref "U3") (pin "54") (pinfunction "VSS_54") (pintype "power_in"))
      (node (ref "U3") (pin "6") (pinfunction "VSSQ_6") (pintype "power_in"))
      (node (ref "U4") (pin "1") (pinfunction "GND_1") (pintype "bidirectional"))
      (node (ref "U5") (pin "1") (pinfunction "GND_1") (pintype "bidirectional"))
      (node (ref "U6") (pin "2") (pinfunction "GND_2") (pintype "bidirectional"))
      (node (ref "U7") (pin "7") (pinfunction "GND_7") (pintype "power_in"))
      (node (ref "USB") (pin "1") (pinfunction "1_1") (pintype "passive"))
    )
    (net (code "185") (name "GPIO1") (class "Default")
      (node (ref "U1") (pin "47") (pinfunction "PA5_47") (pintype "bidirectional"))
    )
    (net (code "186") (name "GPIO2") (class "Default")
      (node (ref "SV1") (pin "21") (pinfunction "21_21") (pintype "passive"))
      (node (ref "U1") (pin "48") (pinfunction "PA6_48") (pintype "bidirectional"))
    )
    (net (code "187") (name "GPIO3") (class "Default")
      (node (ref "DRX") (pin "TP") (pinfunction "TP_TP") (pintype "input"))
      (node (ref "SV1") (pin "22") (pinfunction "22_22") (pintype "passive"))
      (node (ref "U1") (pin "78") (pinfunction "PA30_78") (pintype "bidirectional"))
    )
    (net (code "188") (name "HDMA") (class "Default")
      (node (ref "R10") (pin "1") (pinfunction "1_1") (pintype "passive"))
      (node (ref "U1") (pin "125") (pinfunction "HDMA_125") (pintype "bidirectional"))
    )
    (net (code "189") (name "HDPA") (class "Default")
      (node (ref "R9") (pin "1") (pinfunction "1_1") (pintype "passive"))
      (node (ref "U1") (pin "126") (pinfunction "HDPA_126") (pintype "bidirectional"))
    )
    (net (code "190") (name "HSE_IN") (class "Default")
      (node (ref "C25") (pin "1") (pinfunction "1_1") (pintype "passive"))
      (node (ref "Q1") (pin "1") (pinfunction "1_1") (pintype "passive"))
      (node (ref "U1") (pin "32") (pinfunction "XIN_32") (pintype "input"))
    )
    (net (code "191") (name "HSE_OUT") (class "Default")
      (node (ref "C26") (pin "1") (pinfunction "1_1") (pintype "passive"))
      (node (ref "Q1") (pin "3") (pinfunction "2_3") (pintype "passive"))
      (node (ref "U1") (pin "31") (pinfunction "XOUT_31") (pintype "output"))
    )
    (net (code "192") (name "I2C_SCL") (class "Default")
      (node (ref "R27") (pin "1") (pinfunction "1_1") (pintype "passive"))
      (node (ref "SV1") (pin "17") (pinfunction "17_17") (pintype "passive"))
      (node (ref "U1") (pin "72") (pinfunction "PA26_72") (pintype "bidirectional"))
    )
    (net (code "193") (name "I2C_SDA") (class "Default")
      (node (ref "R26") (pin "1") (pinfunction "1_1") (pintype "passive"))
      (node (ref "SV1") (pin "18") (pinfunction "18_18") (pintype "passive"))
      (node (ref "U1") (pin "71") (pinfunction "PA25_71") (pintype "bidirectional"))
    )
    (net (code "194") (name "IRQ0") (class "Default")
      (node (ref "SV1") (pin "20") (pinfunction "20_20") (pintype "passive"))
      (node (ref "U1") (pin "124") (pinfunction "PB29_124") (pintype "bidirectional"))
    )
    (net (code "195") (name "LED_B") (class "Default")
      (node (ref "R20") (pin "1") (pinfunction "1_1") (pintype "passive"))
      (node (ref "U1") (pin "90") (pinfunction "PB10_90") (pintype "bidirectional"))
    )
    (net (code "196") (name "LED_G") (class "Default")
      (node (ref "R21") (pin "1") (pinfunction "1_1") (pintype "passive"))
      (node (ref "U1") (pin "88") (pinfunction "PB8_88") (pintype "bidirectional"))
    )
    (net (code "197") (name "LED_R") (class "Default")
      (node (ref "R22") (pin "1") (pinfunction "1_1") (pintype "passive"))
      (node (ref "U1") (pin "86") (pinfunction "PB6_86") (pintype "bidirectional"))
    )
    (net (code "198") (name "LSE_IN") (class "Default")
      (node (ref "C27") (pin "1") (pinfunction "1_1") (pintype "passive"))
      (node (ref "Q2") (pin "1") (pinfunction "1_1") (pintype "passive"))
      (node (ref "U1") (pin "36") (pinfunction "XIN32_36") (pintype "input"))
    )
    (net (code "199") (name "LSE_OUT") (class "Default")
      (node (ref "C28") (pin "1") (pinfunction "1_1") (pintype "passive"))
      (node (ref "Q2") (pin "2") (pinfunction "2_2") (pintype "passive"))
      (node (ref "U1") (pin "35") (pinfunction "XOUT32_35") (pintype "output"))
    )
    (net (code "200") (name "MCCDA") (class "Default")
      (node (ref "CON2") (pin "P$3") (pinfunction "CMD_P$3") (pintype "input"))
      (node (ref "R30") (pin "1") (pinfunction "1_1") (pintype "passive"))
      (node (ref "U1") (pin "74") (pinfunction "PA28_74") (pintype "bidirectional"))
    )
    (net (code "202") (name "MCCDT") (class "Default")
      (node (ref "CON2") (pin "P$13") (pinfunction "CD_P$13") (pintype "power_in"))
      (node (ref "R23") (pin "2") (pinfunction "2_2") (pintype "passive"))
      (node (ref "U1") (pin "82") (pinfunction "PB2_82") (pintype "bidirectional"))
    )
    (net (code "203") (name "MCCK") (class "Default")
      (node (ref "CON2") (pin "P$5") (pinfunction "CLK_P$5") (pintype "bidirectional"))
      (node (ref "U1") (pin "73") (pinfunction "PA27_73") (pintype "bidirectional"))
    )
    (net (code "204") (name "MCDA0") (class "Default")
      (node (ref "CON2") (pin "P$7") (pinfunction "DAT0_P$7") (pintype "power_in"))
      (node (ref "R34") (pin "2") (pinfunction "2_2") (pintype "passive"))
      (node (ref "U1") (pin "77") (pinfunction "PA29_77") (pintype "bidirectional"))
    )
    (net (code "205") (name "MCDA1") (class "Default")
      (node (ref "CON2") (pin "P$8") (pinfunction "DAT1_P$8") (pintype "power_in"))
      (node (ref "R35") (pin "2") (pinfunction "2_2") (pintype "passive"))
      (node (ref "U1") (pin "83") (pinfunction "PB3_83") (pintype "bidirectional"))
    )
    (net (code "206") (name "MCDA2") (class "Default")
      (node (ref "CON2") (pin "P$1") (pinfunction "DAT2_P$1") (pintype "output"))
      (node (ref "R31") (pin "2") (pinfunction "2_2") (pintype "passive"))
      (node (ref "U1") (pin "84") (pinfunction "PB4_84") (pintype "bidirectional"))
    )
    (net (code "207") (name "MCDA3") (class "Default")
      (node (ref "CON2") (pin "P$2") (pinfunction "CD/DAT3_P$2") (pintype "input"))
      (node (ref "R32") (pin "2") (pinfunction "2_2") (pintype "passive"))
      (node (ref "U1") (pin "85") (pinfunction "PB5_85") (pintype "bidirectional"))
    )
    (net (code "212") (name "MII_CRSDV") (class "Default")
      (node (ref "RMII") (pin "1") (pinfunction "1_1") (pintype "passive"))
      (node (ref "U1") (pin "53") (pinfunction "PA11_53") (pintype "bidirectional"))
    )
    (net (code "213") (name "MII_ECOL") (class "Default")
      (node (ref "U1") (pin "100") (pinfunction "PB18_100") (pintype "bidirectional"))
    )
    (net (code "214") (name "MII_EMDC") (class "Default")
      (node (ref "RMII") (pin "3") (pinfunction "3_3") (pintype "passive"))
      (node (ref "U1") (pin "59") (pinfunction "PA15_59") (pintype "bidirectional"))
    )
    (net (code "215") (name "MII_EMDIO") (class "Default")
      (node (ref "RMII") (pin "4") (pinfunction "4_4") (pintype "passive"))
      (node (ref "U1") (pin "60") (pinfunction "PA16_60") (pintype "bidirectional"))
    )
    (net (code "216") (name "MII_ERX0") (class "Default")
      (node (ref "RMII") (pin "8") (pinfunction "8_8") (pintype "passive"))
      (node (ref "U1") (pin "54") (pinfunction "PA12_54") (pintype "bidirectional"))
    )
    (net (code "217") (name "MII_ERX1") (class "Default")
      (node (ref "RMII") (pin "7") (pinfunction "7_7") (pintype "passive"))
      (node (ref "U1") (pin "55") (pinfunction "PA13_55") (pintype "bidirectional"))
    )
    (net (code "218") (name "MII_ERXCK") (class "Default")
      (node (ref "U1") (pin "101") (pinfunction "PB19_101") (pintype "bidirectional"))
    )
    (net (code "219") (name "MII_ERXDV") (class "Default")
      (node (ref "U1") (pin "99") (pinfunction "PB17_99") (pintype "bidirectional"))
    )
    (net (code "220") (name "MII_ERXER") (class "Default")
      (node (ref "RMII") (pin "5") (pinfunction "5_5") (pintype "passive"))
      (node (ref "U1") (pin "58") (pinfunction "PA14_58") (pintype "bidirectional"))
    )
    (net (code "221") (name "MII_ETX0") (class "Default")
      (node (ref "RMII") (pin "10") (pinfunction "10_10") (pintype "passive"))
      (node (ref "U1") (pin "51") (pinfunction "PA9_51") (pintype "bidirectional"))
    )
    (net (code "222") (name "MII_ETX1") (class "Default")
      (node (ref "RMII") (pin "9") (pinfunction "9_9") (pintype "passive"))
      (node (ref "U1") (pin "52") (pinfunction "PA10_52") (pintype "bidirectional"))
    )
    (net (code "223") (name "MII_ETXCK") (class "Default")
      (node (ref "RMII") (pin "6") (pinfunction "6_6") (pintype "passive"))
      (node (ref "U1") (pin "49") (pinfunction "PA7_49") (pintype "bidirectional"))
    )
    (net (code "224") (name "MII_ETXEN") (class "Default")
      (node (ref "RMII") (pin "2") (pinfunction "2_2") (pintype "passive"))
      (node (ref "U1") (pin "50") (pinfunction "PA8_50") (pintype "bidirectional"))
    )
    (net (code "225") (name "MII_ETXER") (class "Default")
      (node (ref "U1") (pin "96") (pinfunction "PB14_96") (pintype "bidirectional"))
    )
    (net (code "226") (name "NWAIT") (class "Default")
      (node (ref "R29") (pin "1") (pinfunction "1_1") (pintype "passive"))
      (node (ref "U1") (pin "25") (pinfunction "PC6_25") (pintype "bidirectional"))
    )
    (net (code "227") (name "Net-(C21-Pad1)") (class "Default")
      (node (ref "C21") (pin "1") (pinfunction "1_1") (pintype "passive"))
      (node (ref "R1") (pin "1") (pinfunction "1_1") (pintype "passive"))
    )
    (net (code "228") (name "Net-(C23-Pad1)") (class "Default")
      (node (ref "C23") (pin "1") (pinfunction "1_1") (pintype "passive"))
      (node (ref "R2") (pin "1") (pinfunction "1_1") (pintype "passive"))
    )
    (net (code "229") (name "Net-(CON1-VCC)") (class "Default")
      (node (ref "CON1") (pin "1") (pinfunction "VCC_1") (pintype "bidirectional"))
      (node (ref "F1") (pin "1") (pinfunction "1_1") (pintype "passive"))
    )
    (net (code "230") (name "Net-(IC4-Pad4)") (class "Default")
      (node (ref "IC4") (pin "4") (pinfunction "4_4") (pintype "bidirectional"))
      (node (ref "R14") (pin "2") (pinfunction "2_2") (pintype "passive"))
    )
    (net (code "231") (name "Net-(LED1-Pad1)") (class "Default")
      (node (ref "LED1") (pin "1") (pinfunction "1_1") (pintype "passive"))
      (node (ref "R20") (pin "2") (pinfunction "2_2") (pintype "passive"))
    )
    (net (code "232") (name "Net-(LED1-Pad3)") (class "Default")
      (node (ref "LED1") (pin "3") (pinfunction "3_3") (pintype "passive"))
      (node (ref "R22") (pin "2") (pinfunction "2_2") (pintype "passive"))
    )
    (net (code "233") (name "Net-(LED1-Pad4)") (class "Default")
      (node (ref "LED1") (pin "4") (pinfunction "4_4") (pintype "passive"))
      (node (ref "R21") (pin "2") (pinfunction "2_2") (pintype "passive"))
    )
    (net (code "234") (name "Net-(R7-Pad1)") (class "Default")
      (node (ref "R7") (pin "1") (pinfunction "1_1") (pintype "passive"))
      (node (ref "T1") (pin "E") (pinfunction "E_E") (pintype "passive"))
    )
    (net (code "235") (name "Net-(R13-Pad2)") (class "Default")
      (node (ref "R13") (pin "2") (pinfunction "2_2") (pintype "passive"))
      (node (ref "R16") (pin "1") (pinfunction "1_1") (pintype "passive"))
      (node (ref "R17") (pin "1") (pinfunction "1_1") (pintype "passive"))
    )
    (net (code "236") (name "Net-(R15-Pad2)") (class "Default")
      (node (ref "R15") (pin "2") (pinfunction "2_2") (pintype "passive"))
      (node (ref "R18") (pin "1") (pinfunction "1_1") (pintype "passive"))
      (node (ref "R19") (pin "1") (pinfunction "1_1") (pintype "passive"))
    )
    (net (code "237") (name "Net-(U4-BST)") (class "Default")
      (node (ref "C56") (pin "1") (pinfunction "1_1") (pintype "passive"))
      (node (ref "U4") (pin "6") (pinfunction "BST_6") (pintype "bidirectional"))
    )
    (net (code "238") (name "Net-(U4-FB)") (class "Default")
      (node (ref "R13") (pin "1") (pinfunction "1_1") (pintype "passive"))
      (node (ref "U4") (pin "4") (pinfunction "FB_4") (pintype "bidirectional"))
    )
    (net (code "239") (name "Net-(U4-SW)") (class "Default")
      (node (ref "C56") (pin "2") (pinfunction "2_2") (pintype "passive"))
      (node (ref "L1") (pin "1") (pinfunction "1_1") (pintype "passive"))
      (node (ref "U4") (pin "2") (pinfunction "SW_2") (pintype "bidirectional"))
    )
    (net (code "240") (name "Net-(U5-BST)") (class "Default")
      (node (ref "C57") (pin "1") (pinfunction "1_1") (pintype "passive"))
      (node (ref "U5") (pin "6") (pinfunction "BST_6") (pintype "bidirectional"))
    )
    (net (code "241") (name "Net-(U5-FB)") (class "Default")
      (node (ref "R15") (pin "1") (pinfunction "1_1") (pintype "passive"))
      (node (ref "U5") (pin "4") (pinfunction "FB_4") (pintype "bidirectional"))
    )
    (net (code "242") (name "Net-(U5-SW)") (class "Default")
      (node (ref "C57") (pin "2") (pinfunction "2_2") (pintype "passive"))
      (node (ref "L2") (pin "1") (pinfunction "1_1") (pintype "passive"))
      (node (ref "U5") (pin "2") (pinfunction "SW_2") (pintype "bidirectional"))
    )
    (net (code "243") (name "Net-(U6-CD)") (class "Default")
      (node (ref "C44") (pin "1") (pinfunction "1_1") (pintype "passive"))
      (node (ref "U6") (pin "5") (pinfunction "CD_5") (pintype "bidirectional"))
    )
    (net (code "244") (name "Net-(U7-{slash}WP)") (class "Default")
      (node (ref "R28") (pin "1") (pinfunction "1_1") (pintype "passive"))
      (node (ref "U7") (pin "5") (pinfunction "/WP_5") (pintype "input"))
    )
    (net (code "245") (name "PLLRCA") (class "Default")
      (node (ref "C22") (pin "1") (pinfunction "1_1") (pintype "passive"))
      (node (ref "R1") (pin "2") (pinfunction "2_2") (pintype "passive"))
      (node (ref "U1") (pin "29") (pinfunction "PLLRCA_29") (pintype "input"))
    )
    (net (code "246") (name "PLLRCB") (class "Default")
      (node (ref "C24") (pin "1") (pinfunction "1_1") (pintype "passive"))
      (node (ref "R2") (pin "2") (pinfunction "2_2") (pintype "passive"))
      (node (ref "U1") (pin "38") (pinfunction "PLLRCB_38") (pintype "input"))
    )
    (net (code "247") (name "RAS") (class "Default")
      (node (ref "U1") (pin "176") (pinfunction "RAS_176") (pintype "bidirectional"))
      (node (ref "U2") (pin "18") (pinfunction "~{RAS}_18") (pintype "input"))
      (node (ref "U3") (pin "18") (pinfunction "~{RAS}_18") (pintype "input"))
    )
    (net (code "248") (name "SDA10") (class "Default")
      (node (ref "U1") (pin "144") (pinfunction "SDA10_144") (pintype "bidirectional"))
      (node (ref "U2") (pin "22") (pinfunction "A10_22") (pintype "input"))
      (node (ref "U3") (pin "22") (pinfunction "A10_22") (pintype "input"))
    )
    (net (code "249") (name "SDCK") (class "Default")
      (node (ref "U1") (pin "174") (pinfunction "SDCK_174") (pintype "bidirectional"))
      (node (ref "U2") (pin "38") (pinfunction "CLK_38") (pintype "input"))
      (node (ref "U3") (pin "38") (pinfunction "CLK_38") (pintype "input"))
    )
    (net (code "250") (name "SDCKE") (class "Default")
      (node (ref "U1") (pin "175") (pinfunction "SDCKE_175") (pintype "bidirectional"))
      (node (ref "U2") (pin "37") (pinfunction "CKE_37") (pintype "input"))
      (node (ref "U3") (pin "37") (pinfunction "CKE_37") (pintype "input"))
    )
    (net (code "251") (name "SDCS") (class "Default")
      (node (ref "U1") (pin "167") (pinfunction "NCS1/SDCS_167") (pintype "bidirectional"))
      (node (ref "U2") (pin "19") (pinfunction "\\CS_19") (pintype "input"))
      (node (ref "U3") (pin "19") (pinfunction "\\CS_19") (pintype "input"))
    )
    (net (code "252") (name "SDWE") (class "Default")
      (node (ref "U1") (pin "178") (pinfunction "SDWE_178") (pintype "bidirectional"))
      (node (ref "U2") (pin "16") (pinfunction "~{WE}_16") (pintype "input"))
      (node (ref "U3") (pin "16") (pinfunction "~{WE}_16") (pintype "input"))
    )
    (net (code "253") (name "SPI_CLK") (class "Default")
      (node (ref "SV1") (pin "25") (pinfunction "25_25") (pintype "passive"))
      (node (ref "U1") (pin "44") (pinfunction "PA2_44") (pintype "bidirectional"))
      (node (ref "U7") (pin "2") (pinfunction "SCK_2") (pintype "input"))
    )
    (net (code "254") (name "SPI_CSB") (class "Default")
      (node (ref "U1") (pin "45") (pinfunction "PA3_45") (pintype "bidirectional"))
      (node (ref "U7") (pin "4") (pinfunction "/CS_4") (pintype "input"))
    )
    (net (code "255") (name "SPI_MISO") (class "Default")
      (node (ref "SV1") (pin "28") (pinfunction "28_28") (pintype "passive"))
      (node (ref "U1") (pin "42") (pinfunction "PA0_42") (pintype "bidirectional"))
      (node (ref "U7") (pin "8") (pinfunction "SO_8") (pintype "output"))
    )
    (net (code "256") (name "SPI_MOSI") (class "Default")
      (node (ref "SV1") (pin "27") (pinfunction "27_27") (pintype "passive"))
      (node (ref "U1") (pin "43") (pinfunction "PA1_43") (pintype "bidirectional"))
      (node (ref "U7") (pin "1") (pinfunction "SI_1") (pintype "input"))
    )
    (net (code "257") (name "SPI_NSS") (class "Default")
      (node (ref "SV1") (pin "26") (pinfunction "26_26") (pintype "passive"))
      (node (ref "U1") (pin "46") (pinfunction "PA4_46") (pintype "bidirectional"))
    )
    (net (code "258") (name "UART_RXD0") (class "Default")
      (node (ref "SV1") (pin "12") (pinfunction "12_12") (pintype "passive"))
      (node (ref "U1") (pin "64") (pinfunction "PA18_64") (pintype "bidirectional"))
    )
    (net (code "259") (name "UART_RXD1") (class "Default")
      (node (ref "SV1") (pin "16") (pinfunction "16_16") (pintype "passive"))
      (node (ref "U1") (pin "103") (pinfunction "PB21_103") (pintype "bidirectional"))
    )
    (net (code "260") (name "UART_RXD2") (class "Default")
      (node (ref "SV1") (pin "24") (pinfunction "24_24") (pintype "passive"))
      (node (ref "U1") (pin "68") (pinfunction "PA22_68") (pintype "bidirectional"))
    )
    (net (code "261") (name "UART_TXD0") (class "Default")
      (node (ref "SV1") (pin "11") (pinfunction "11_11") (pintype "passive"))
      (node (ref "U1") (pin "61") (pinfunction "PA17_61") (pintype "bidirectional"))
    )
    (net (code "262") (name "UART_TXD1") (class "Default")
      (node (ref "SV1") (pin "15") (pinfunction "15_15") (pintype "passive"))
      (node (ref "U1") (pin "102") (pinfunction "PB20_102") (pintype "bidirectional"))
    )
    (net (code "263") (name "UART_TXD2") (class "Default")
      (node (ref "SV1") (pin "23") (pinfunction "23_23") (pintype "passive"))
      (node (ref "U1") (pin "69") (pinfunction "PA23_69") (pintype "bidirectional"))
    )
    (net (code "264") (name "USBC_DM") (class "Default")
      (node (ref "C50") (pin "1") (pinfunction "1_1") (pintype "passive"))
      (node (ref "CON1") (pin "2") (pinfunction "DM_2") (pintype "bidirectional"))
      (node (ref "R5") (pin "1") (pinfunction "1_1") (pintype "passive"))
    )
    (net (code "265") (name "USBC_DP") (class "Default")
      (node (ref "C50") (pin "2") (pinfunction "2_2") (pintype "passive"))
      (node (ref "CON1") (pin "3") (pinfunction "DP_3") (pintype "bidirectional"))
      (node (ref "R6") (pin "1") (pinfunction "1_1") (pintype "passive"))
      (node (ref "R7") (pin "2") (pinfunction "2_2") (pintype "passive"))
    )
    (net (code "266") (name "USBC_ID") (class "Default")
      (node (ref "CON1") (pin "4") (pinfunction "ID_4") (pintype "bidirectional"))
      (node (ref "R24") (pin "1") (pinfunction "1_1") (pintype "passive"))
      (node (ref "U1") (pin "66") (pinfunction "PA20_66") (pintype "bidirectional"))
    )
    (net (code "267") (name "USB_C_DM") (class "Default")
      (node (ref "C48") (pin "1") (pinfunction "1_1") (pintype "passive"))
      (node (ref "R5") (pin "2") (pinfunction "2_2") (pintype "passive"))
      (node (ref "U1") (pin "127") (pinfunction "DDM_127") (pintype "bidirectional"))
    )
    (net (code "268") (name "USB_C_DP") (class "Default")
      (node (ref "C49") (pin "1") (pinfunction "1_1") (pintype "passive"))
      (node (ref "R6") (pin "2") (pinfunction "2_2") (pintype "passive"))
      (node (ref "U1") (pin "128") (pinfunction "DDP_128") (pintype "bidirectional"))
    )
    (net (code "269") (name "USB_DP_PUP") (class "Default")
      (node (ref "D1") (pin "A") (pinfunction "A_A") (pintype "passive"))
      (node (ref "R8") (pin "1") (pinfunction "1_1") (pintype "passive"))
      (node (ref "T1") (pin "B") (pinfunction "B_B") (pintype "passive"))
      (node (ref "U1") (pin "65") (pinfunction "PA19_65") (pintype "bidirectional"))
    )
    (net (code "270") (name "USB_H1_DM") (class "Default")
      (node (ref "C51") (pin "1") (pinfunction "1_1") (pintype "passive"))
      (node (ref "R10") (pin "2") (pinfunction "2_2") (pintype "passive"))
      (node (ref "R11") (pin "2") (pinfunction "2_2") (pintype "passive"))
      (node (ref "USB") (pin "2") (pinfunction "2_2") (pintype "passive"))
    )
    (net (code "271") (name "USB_H1_DP") (class "Default")
      (node (ref "C52") (pin "1") (pinfunction "1_1") (pintype "passive"))
      (node (ref "R12") (pin "2") (pinfunction "2_2") (pintype "passive"))
      (node (ref "R9") (pin "2") (pinfunction "2_2") (pintype "passive"))
      (node (ref "USB") (pin "3") (pinfunction "3_3") (pintype "passive"))
    )
    (net (code "272") (name "USB_H2_DM") (class "Default")
      (node (ref "USB") (pin "4") (pinfunction "4_4") (pintype "passive"))
    )
    (net (code "273") (name "USB_H2_DP") (class "Default")
      (node (ref "USB") (pin "5") (pinfunction "5_5") (pintype "passive"))
    )
    (net (code "274") (name "USB_VCC") (class "Default")
      (node (ref "C45") (pin "1") (pinfunction "1_1") (pintype "passive"))
      (node (ref "F1") (pin "2") (pinfunction "2_2") (pintype "passive"))
      (node (ref "IC4") (pin "6") (pinfunction "IN2_6") (pintype "bidirectional"))
      (node (ref "J1") (pin "1") (pinfunction "1_1") (pintype "passive"))
      (node (ref "R37") (pin "2") (pinfunction "2_2") (pintype "passive"))
    )
    (net (code "275") (name "USB_VDET") (class "Default")
      (node (ref "R36") (pin "2") (pinfunction "2_2") (pintype "passive"))
      (node (ref "R37") (pin "1") (pinfunction "1_1") (pintype "passive"))
      (node (ref "U1") (pin "67") (pinfunction "PA21_67") (pintype "bidirectional"))
    )
    (net (code "276") (name "VBAT") (class "Default")
      (node (ref "SV1") (pin "4") (pinfunction "4_4") (pintype "passive"))
    )
    (net (code "277") (name "VEXT") (class "Default")
      (node (ref "C47") (pin "1") (pinfunction "1_1") (pintype "passive"))
      (node (ref "IC4") (pin "8") (pinfunction "IN1_8") (pintype "bidirectional"))
      (node (ref "J2") (pin "2") (pinfunction "2_2") (pintype "passive"))
      (node (ref "SV1") (pin "2") (pinfunction "2_2") (pintype "passive"))
    )
    (net (code "278") (name "unconnected-(IC4-Pad1)") (class "Default")
      (node (ref "IC4") (pin "1") (pinfunction "1_1") (pintype "bidirectional"))
    )
    (net (code "279") (name "unconnected-(IC4-Pad2)") (class "Default")
      (node (ref "IC4") (pin "2") (pinfunction "2_2") (pintype "bidirectional"))
    )
    (net (code "280") (name "unconnected-(SV1-Pad5)") (class "Default")
      (node (ref "SV1") (pin "5") (pinfunction "5_5") (pintype "passive"))
    )
    (net (code "281") (name "unconnected-(SV1-Pad6)") (class "Default")
      (node (ref "SV1") (pin "6") (pinfunction "6_6") (pintype "passive"))
    )
    (net (code "282") (name "unconnected-(SV1-Pad8)") (class "Default")
      (node (ref "SV1") (pin "8") (pinfunction "8_8") (pintype "passive"))
    )
    (net (code "283") (name "unconnected-(SV1-Pad9)") (class "Default")
      (node (ref "SV1") (pin "9") (pinfunction "9_9") (pintype "passive"))
    )
    (net (code "284") (name "unconnected-(SV1-Pad10)") (class "Default")
      (node (ref "SV1") (pin "10") (pinfunction "10_10") (pintype "passive"))
    )
    (net (code "285") (name "unconnected-(TP3-PadTP)") (class "Default")
      (node (ref "TP3") (pin "TP") (pinfunction "TP_TP") (pintype "input"))
    )
    (net (code "286") (name "unconnected-(U1-A12-Pad148)") (class "Default")
      (node (ref "U1") (pin "148") (pinfunction "A12_148") (pintype "output"))
    )
    (net (code "287") (name "unconnected-(U1-A15-Pad151)") (class "Default")
      (node (ref "U1") (pin "151") (pinfunction "A15_151") (pintype "output"))
    )
    (net (code "288") (name "unconnected-(U1-A18-Pad156)") (class "Default")
      (node (ref "U1") (pin "156") (pinfunction "A18_156") (pintype "output"))
    )
    (net (code "289") (name "unconnected-(U1-A19-Pad157)") (class "Default")
      (node (ref "U1") (pin "157") (pinfunction "A19_157") (pintype "output"))
    )
    (net (code "290") (name "unconnected-(U1-A20-Pad158)") (class "Default")
      (node (ref "U1") (pin "158") (pinfunction "A20_158") (pintype "output"))
    )
    (net (code "291") (name "unconnected-(U1-A21-Pad159)") (class "Default")
      (node (ref "U1") (pin "159") (pinfunction "A21_159") (pintype "output"))
    )
    (net (code "292") (name "unconnected-(U1-A22-Pad160)") (class "Default")
      (node (ref "U1") (pin "160") (pinfunction "A22_160") (pintype "output"))
    )
    (net (code "293") (name "unconnected-(U1-NCS0{slash}BFCS-Pad166)") (class "Default")
      (node (ref "U1") (pin "166") (pinfunction "NCS0/BFCS_166") (pintype "bidirectional"))
    )
    (net (code "294") (name "unconnected-(U1-NCS2-Pad168)") (class "Default")
      (node (ref "U1") (pin "168") (pinfunction "NCS2_168") (pintype "bidirectional"))
    )
    (net (code "295") (name "unconnected-(U1-NCS3{slash}SMCS-Pad169)") (class "Default")
      (node (ref "U1") (pin "169") (pinfunction "NCS3/SMCS_169") (pintype "bidirectional"))
    )
    (net (code "296") (name "unconnected-(U1-NRD{slash}NOE{slash}CFOE-Pad170)") (class "Default")
      (node (ref "U1") (pin "170") (pinfunction "NRD/NOE/CFOE_170") (pintype "bidirectional"))
    )
    (net (code "297") (name "unconnected-(U1-NWR0{slash}NWE{slash}CFWE-Pad171)") (class "Default")
      (node (ref "U1") (pin "171") (pinfunction "NWR0/NWE/CFWE_171") (pintype "bidirectional"))
    )
    (net (code "298") (name "unconnected-(U1-PA24-Pad70)") (class "Default")
      (node (ref "U1") (pin "70") (pinfunction "PA24_70") (pintype "bidirectional"))
    )
    (net (code "299") (name "unconnected-(U1-PB7-Pad87)") (class "Default")
      (node (ref "U1") (pin "87") (pinfunction "PB7_87") (pintype "bidirectional"))
    )
    (net (code "300") (name "unconnected-(U1-PB9-Pad89)") (class "Default")
      (node (ref "U1") (pin "89") (pinfunction "PB9_89") (pintype "bidirectional"))
    )
    (net (code "301") (name "unconnected-(U1-PB11-Pad91)") (class "Default")
      (node (ref "U1") (pin "91") (pinfunction "PB11_91") (pintype "bidirectional"))
    )
    (net (code "302") (name "unconnected-(U1-PB12-Pad92)") (class "Default")
      (node (ref "U1") (pin "92") (pinfunction "PB12_92") (pintype "bidirectional"))
    )
    (net (code "303") (name "unconnected-(U1-PB13-Pad95)") (class "Default")
      (node (ref "U1") (pin "95") (pinfunction "PB13_95") (pintype "bidirectional"))
    )
    (net (code "304") (name "unconnected-(U1-PB15-Pad97)") (class "Default")
      (node (ref "U1") (pin "97") (pinfunction "PB15_97") (pintype "bidirectional"))
    )
    (net (code "305") (name "unconnected-(U1-PB16-Pad98)") (class "Default")
      (node (ref "U1") (pin "98") (pinfunction "PB16_98") (pintype "bidirectional"))
    )
    (net (code "306") (name "unconnected-(U1-PB22-Pad104)") (class "Default")
      (node (ref "U1") (pin "104") (pinfunction "PB22_104") (pintype "bidirectional"))
    )
    (net (code "307") (name "unconnected-(U1-PB23-Pad118)") (class "Default")
      (node (ref "U1") (pin "118") (pinfunction "PB23_118") (pintype "bidirectional"))
    )
    (net (code "308") (name "unconnected-(U1-PB24-Pad119)") (class "Default")
      (node (ref "U1") (pin "119") (pinfunction "PB24_119") (pintype "bidirectional"))
    )
    (net (code "309") (name "unconnected-(U1-PB25-Pad120)") (class "Default")
      (node (ref "U1") (pin "120") (pinfunction "PB25_120") (pintype "bidirectional"))
    )
    (net (code "310") (name "unconnected-(U1-PB26-Pad121)") (class "Default")
      (node (ref "U1") (pin "121") (pinfunction "PB26_121") (pintype "bidirectional"))
    )
    (net (code "311") (name "unconnected-(U1-PB27-Pad122)") (class "Default")
      (node (ref "U1") (pin "122") (pinfunction "PB27_122") (pintype "bidirectional"))
    )
    (net (code "312") (name "unconnected-(U1-PC8-Pad162)") (class "Default")
      (node (ref "U1") (pin "162") (pinfunction "PC8_162") (pintype "bidirectional"))
    )
    (net (code "313") (name "unconnected-(U1-PC11-Pad12)") (class "Default")
      (node (ref "U1") (pin "12") (pinfunction "PC11_12") (pintype "bidirectional"))
    )
    (net (code "314") (name "unconnected-(U1-PC12-Pad13)") (class "Default")
      (node (ref "U1") (pin "13") (pinfunction "PC12_13") (pintype "bidirectional"))
    )
    (net (code "315") (name "unconnected-(U1-PC13-Pad14)") (class "Default")
      (node (ref "U1") (pin "14") (pinfunction "PC13_14") (pintype "bidirectional"))
    )
    (net (code "316") (name "unconnected-(U1-PC14-Pad15)") (class "Default")
      (node (ref "U1") (pin "15") (pinfunction "PC14_15") (pintype "bidirectional"))
    )
    (net (code "317") (name "unconnected-(U1-PC15-Pad16)") (class "Default")
      (node (ref "U1") (pin "16") (pinfunction "PC15_16") (pintype "bidirectional"))
    )
    (net (code "318") (name "unconnected-(U1-TCK-Pad108)") (class "Default")
      (node (ref "U1") (pin "108") (pinfunction "TCK_108") (pintype "input"))
    )
    (net (code "319") (name "unconnected-(U1-TDI-Pad106)") (class "Default")
      (node (ref "U1") (pin "106") (pinfunction "TDI_106") (pintype "input"))
    )
    (net (code "320") (name "unconnected-(U1-TDO-Pad107)") (class "Default")
      (node (ref "U1") (pin "107") (pinfunction "TDO_107") (pintype "output"))
    )
    (net (code "321") (name "unconnected-(U1-TMS-Pad109)") (class "Default")
      (node (ref "U1") (pin "109") (pinfunction "TMS_109") (pintype "input"))
    )
    (net (code "322") (name "unconnected-(U2A-NC-Pad40)") (class "Default")
      (node (ref "U2") (pin "40") (pinfunction "NC_40") (pintype "no_connect"))
    )
    (net (code "323") (name "unconnected-(U3A-NC-Pad40)") (class "Default")
      (node (ref "U3") (pin "40") (pinfunction "NC_40") (pintype "no_connect"))
    )
    (net (code "324") (name "~{MRST}") (class "Default")
      (node (ref "R3") (pin "2") (pinfunction "2_2") (pintype "passive"))
      (node (ref "TP2") (pin "TP") (pinfunction "TP_TP") (pintype "input"))
      (node (ref "U6") (pin "4") (pinfunction "VSEN_4") (pintype "bidirectional"))
    )
    (net (code "325") (name "~{RST}") (class "Default")
      (node (ref "D1") (pin "K") (pinfunction "C_K") (pintype "passive"))
      (node (ref "R4") (pin "2") (pinfunction "2_2") (pintype "passive"))
      (node (ref "SV1") (pin "7") (pinfunction "7_7") (pintype "passive"))
      (node (ref "U1") (pin "110") (pinfunction "~{NTRST}_110") (pintype "input"))
      (node (ref "U1") (pin "115") (pinfunction "~{NRST}_115") (pintype "input"))
      (node (ref "U6") (pin "1") (pinfunction "~{RST}_1") (pintype "bidirectional"))
      (node (ref "U7") (pin "3") (pinfunction "/RST_3") (pintype "input"))
    )
  )
)
